# blinds_v60.net
KiCad netlist of a schematic drawn in EAGLE
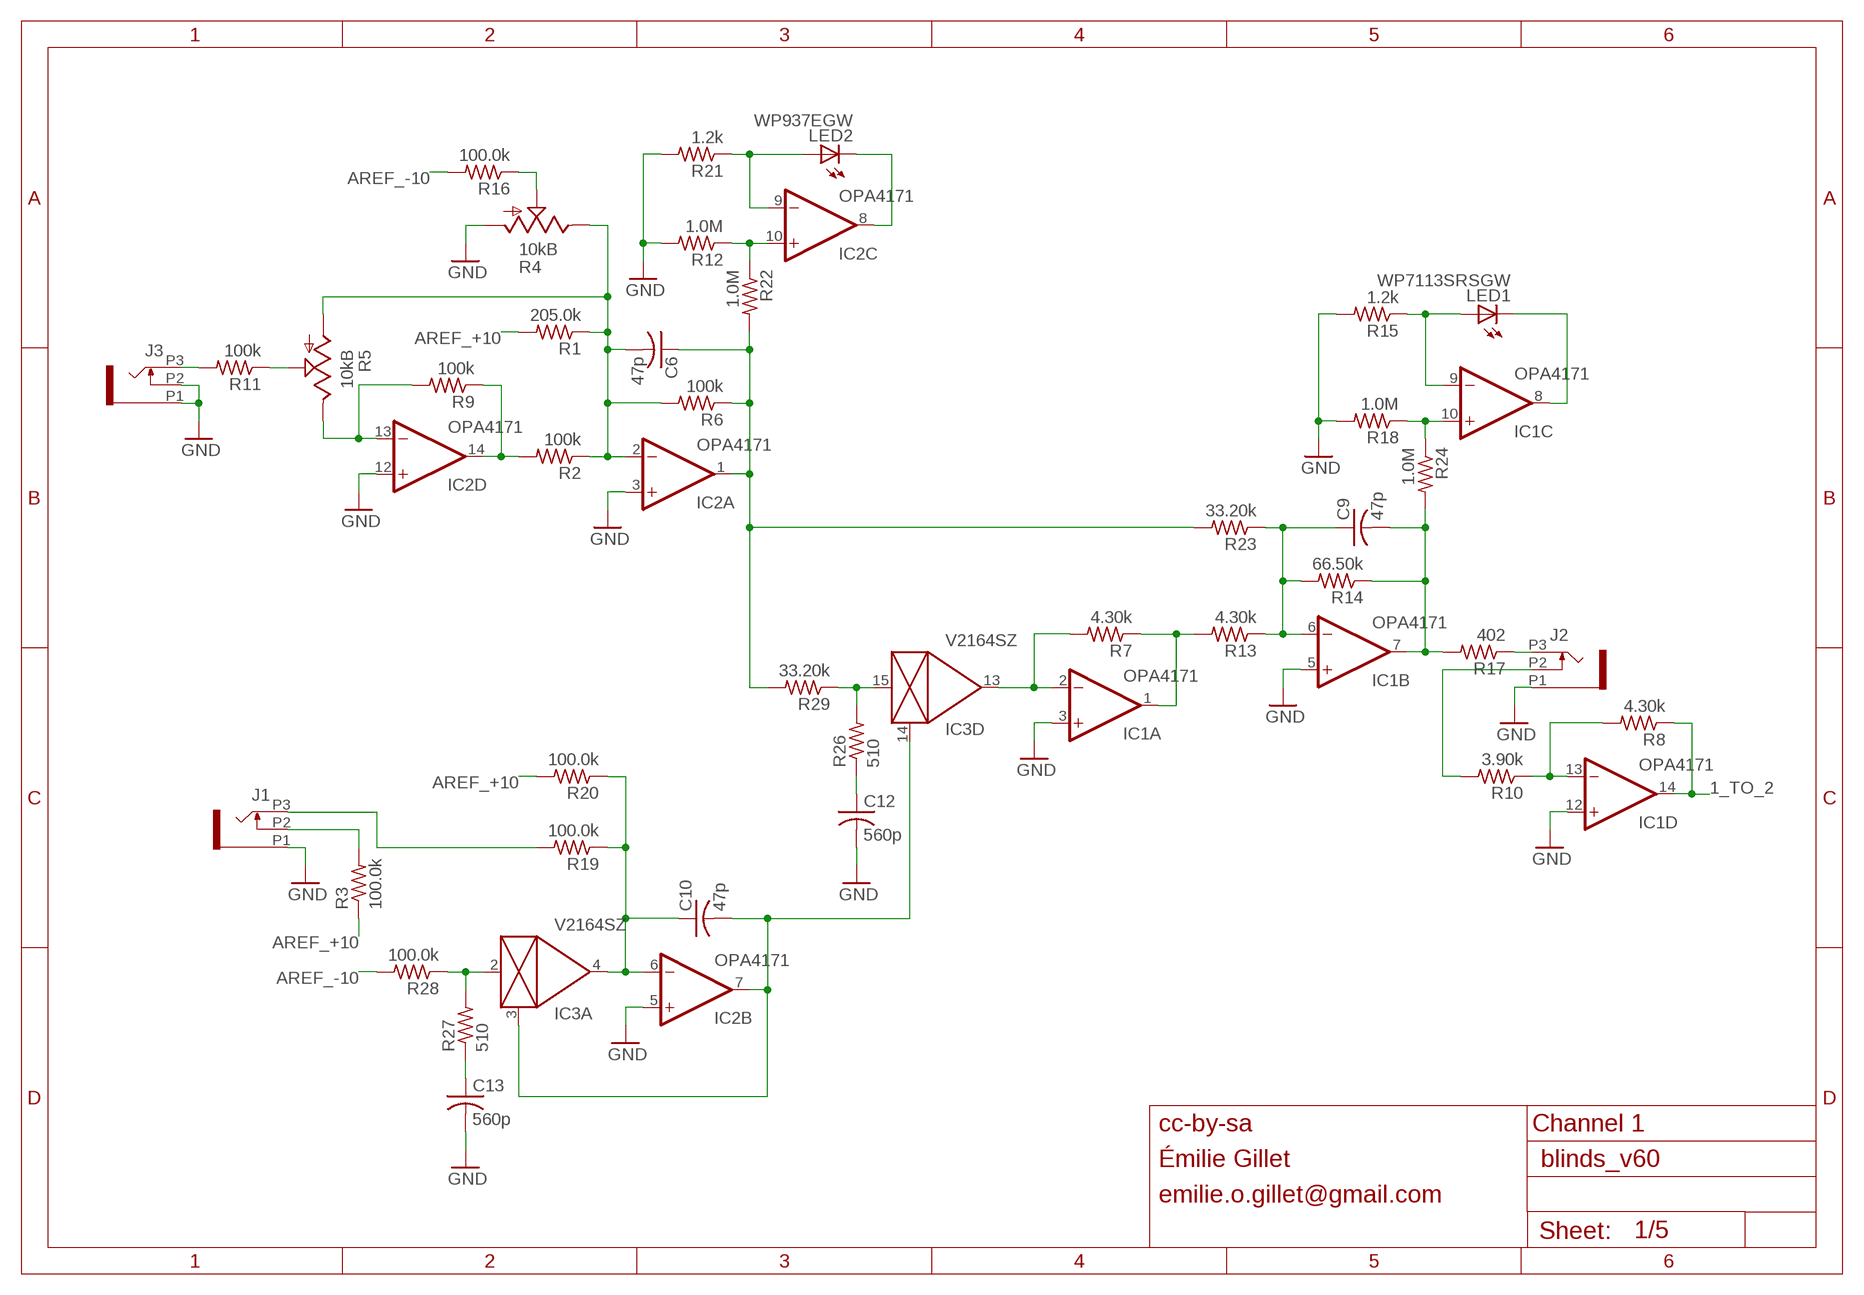
[diagram p0: schematic, sheet 1]
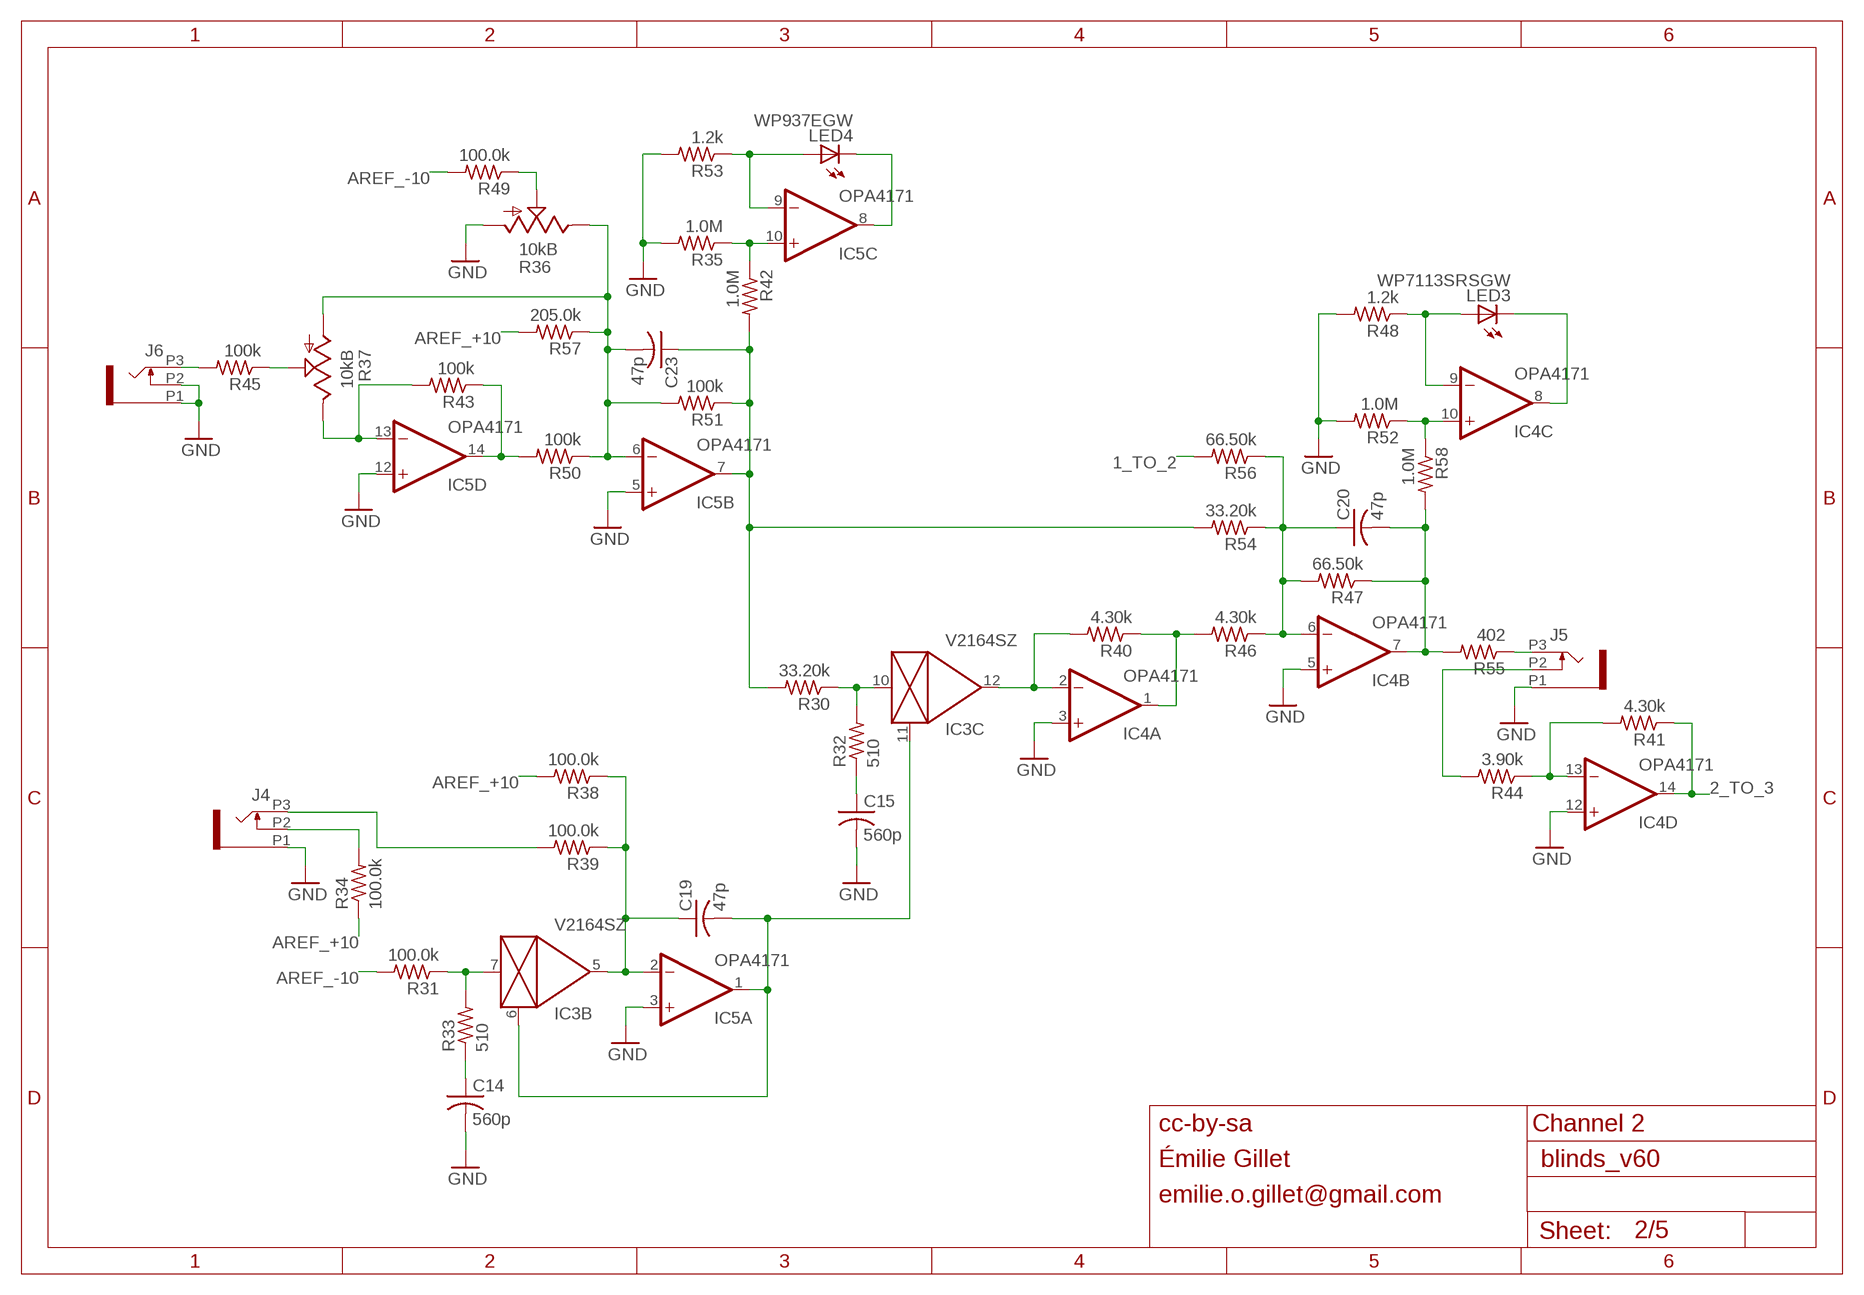
[diagram p1: schematic, sheet 2]
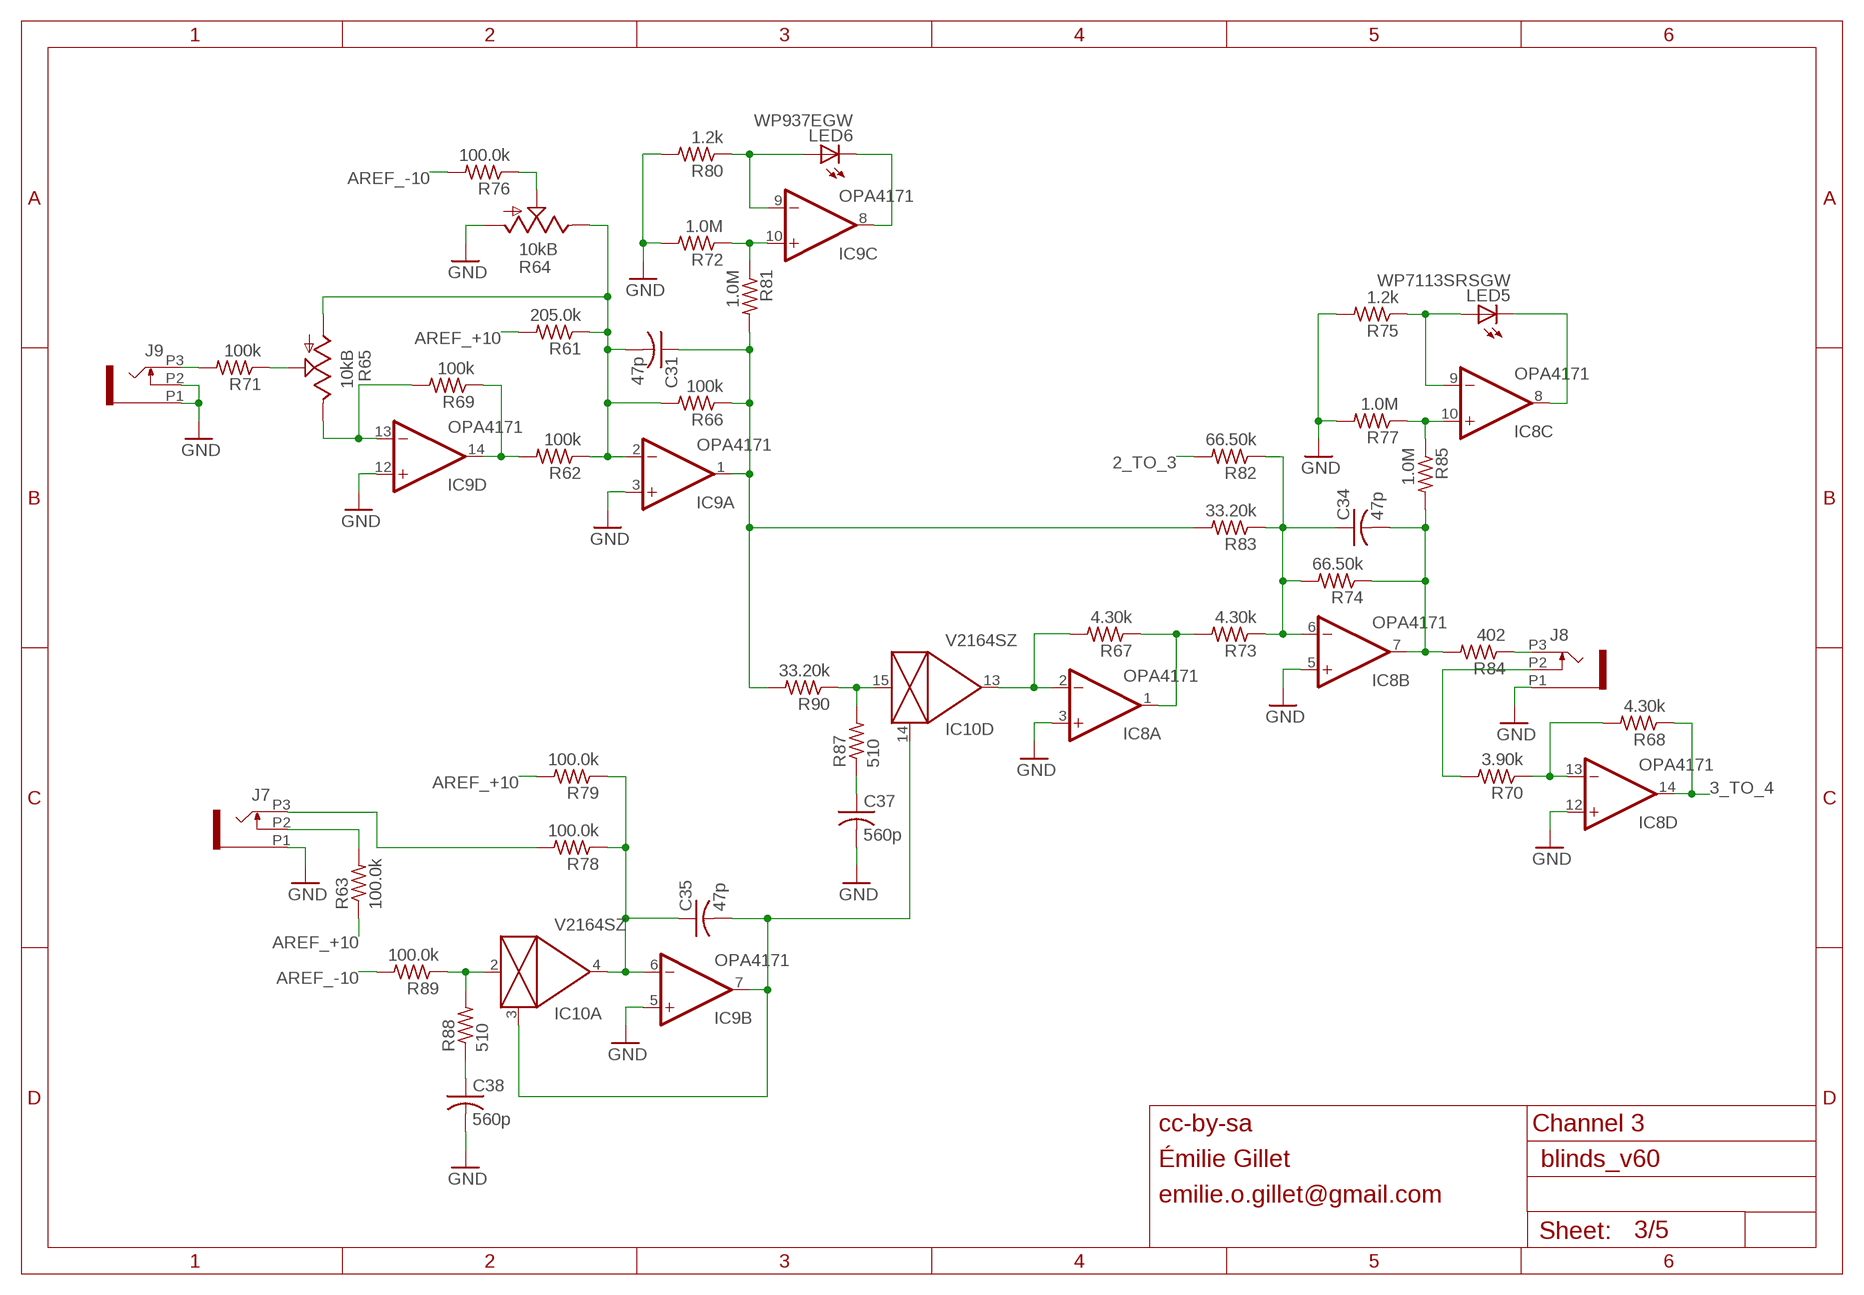
[diagram p2: schematic, sheet 3]
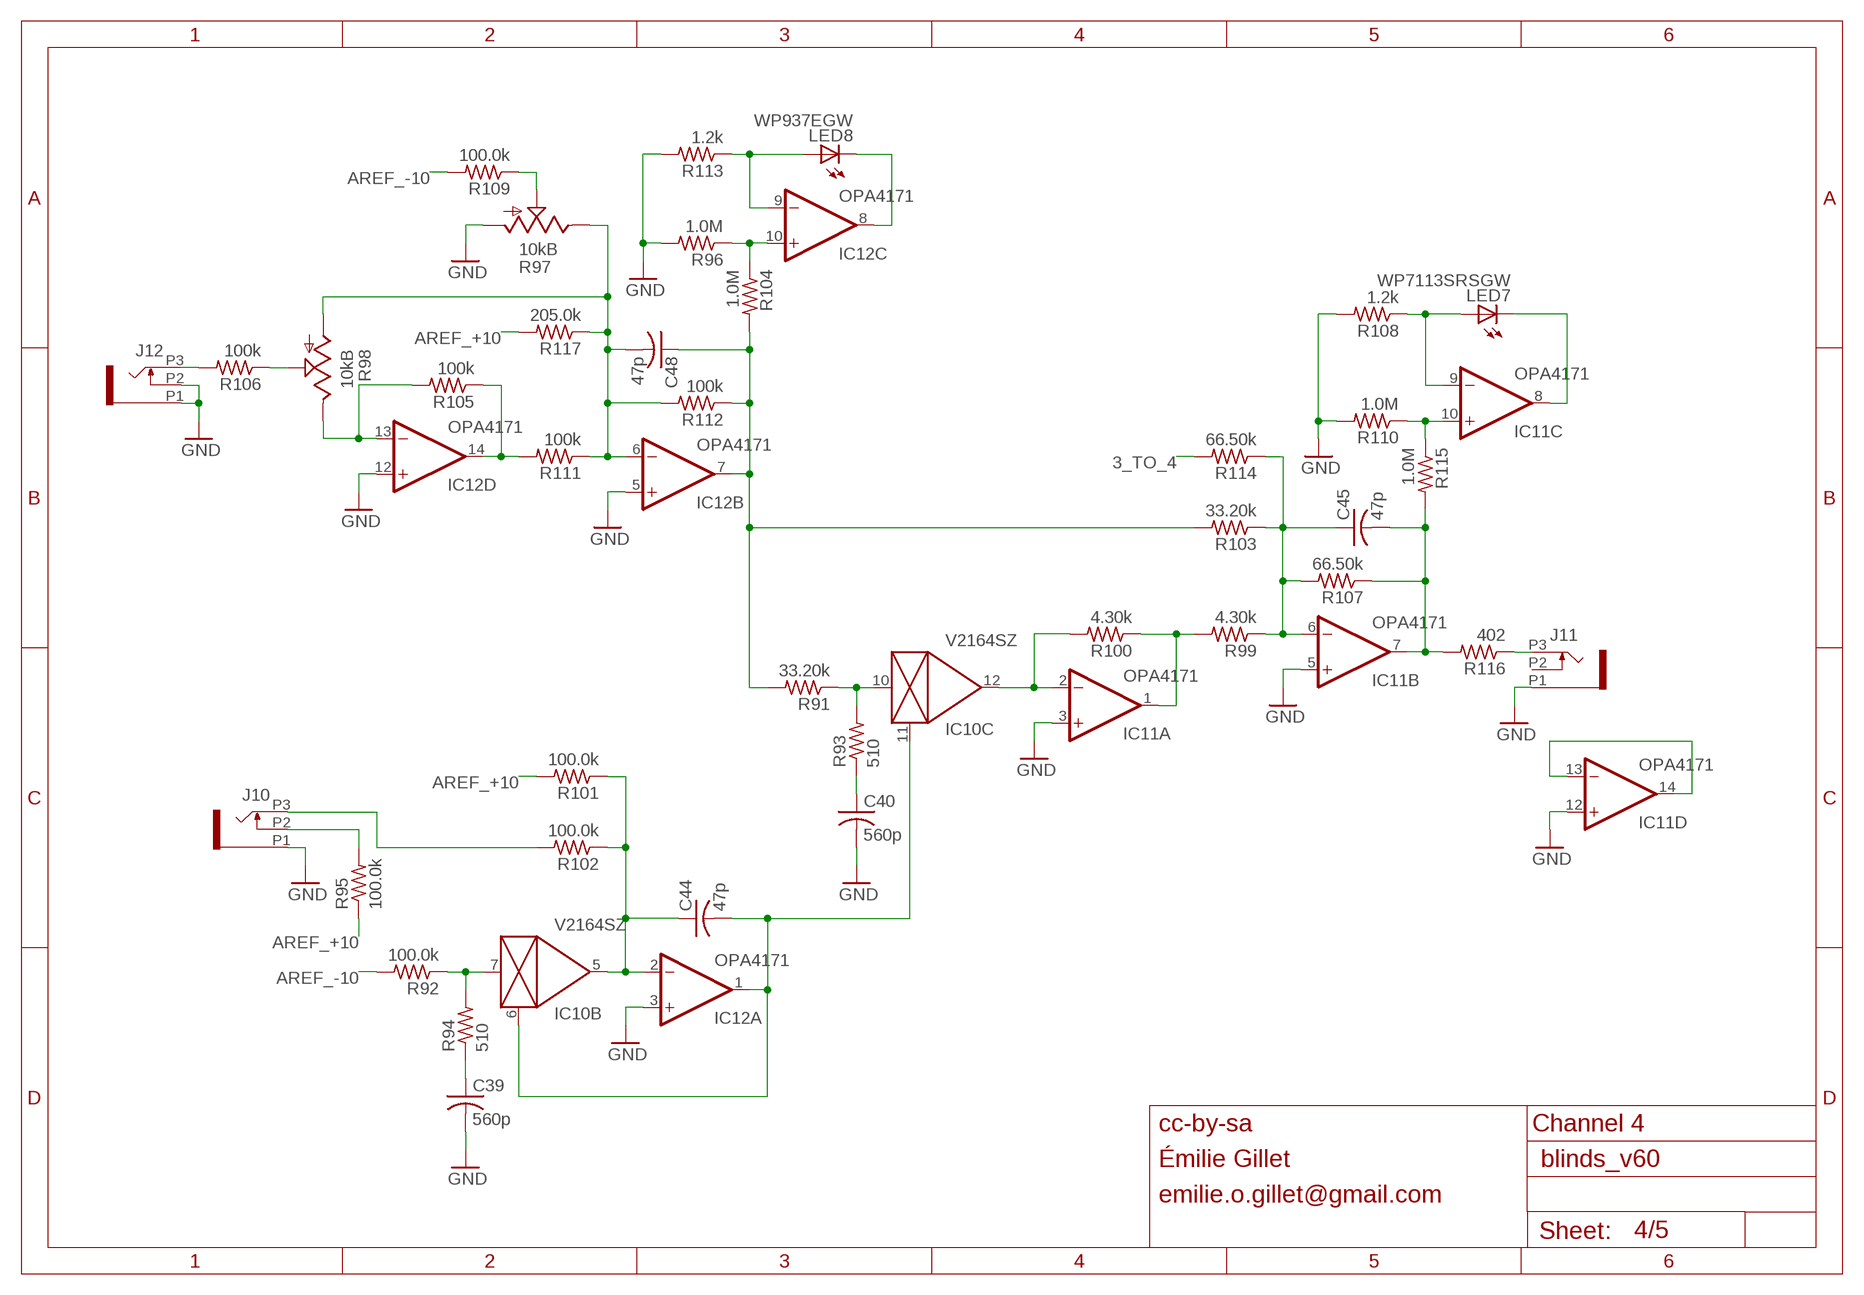
[diagram p3: schematic, sheet 4]
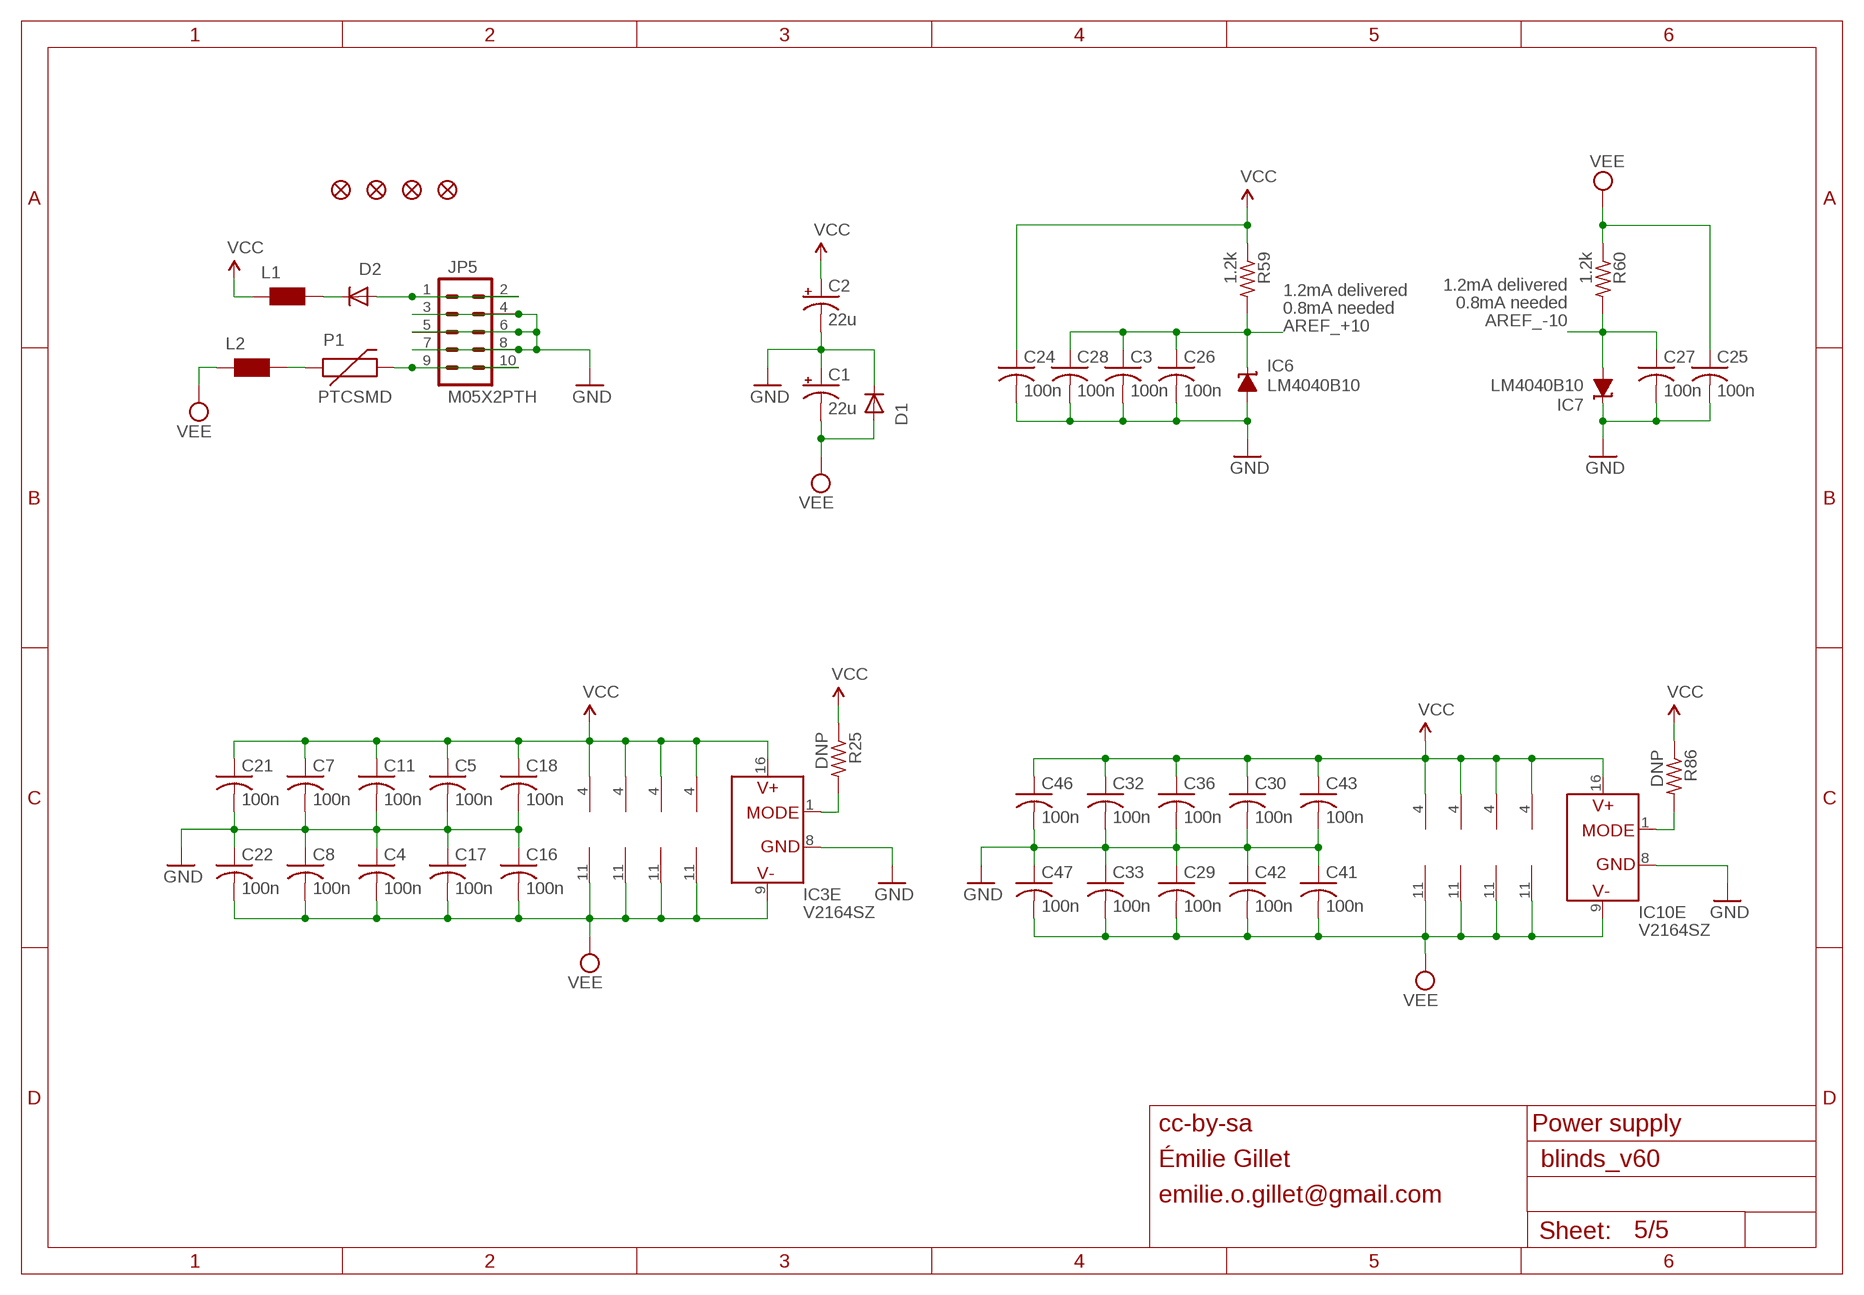
[diagram p4: schematic, sheet 5]

(export (version "E")
  (design (tool "Eeschema 10.0.6"))
  (components
    (comp (ref "C1")
      (value "22u")
      (footprint "eagle-import:PANASONIC_C")
      (libsource (lib "eagle-import") (part "CPOL-USC"))
    )
    (comp (ref "C2")
      (value "22u")
      (footprint "eagle-import:PANASONIC_C")
      (libsource (lib "eagle-import") (part "CPOL-USC"))
    )
    (comp (ref "C3")
      (value "100n")
      (footprint "eagle-import:C0603")
      (libsource (lib "eagle-import") (part "C-USC0603"))
    )
    (comp (ref "C4")
      (value "100n")
      (footprint "eagle-import:C0603")
      (libsource (lib "eagle-import") (part "C-USC0603"))
    )
    (comp (ref "C5")
      (value "100n")
      (footprint "eagle-import:C0603")
      (libsource (lib "eagle-import") (part "C-USC0603"))
    )
    (comp (ref "C7")
      (value "100n")
      (footprint "eagle-import:C0603")
      (libsource (lib "eagle-import") (part "C-USC0603"))
    )
    (comp (ref "C8")
      (value "100n")
      (footprint "eagle-import:C0603")
      (libsource (lib "eagle-import") (part "C-USC0603"))
    )
    (comp (ref "C11")
      (value "100n")
      (footprint "eagle-import:C0603")
      (libsource (lib "eagle-import") (part "C-USC0603"))
    )
    (comp (ref "C16")
      (value "100n")
      (footprint "eagle-import:C0603")
      (libsource (lib "eagle-import") (part "C-USC0603"))
    )
    (comp (ref "C17")
      (value "100n")
      (footprint "eagle-import:C0603")
      (libsource (lib "eagle-import") (part "C-USC0603"))
    )
    (comp (ref "C18")
      (value "100n")
      (footprint "eagle-import:C0603")
      (libsource (lib "eagle-import") (part "C-USC0603"))
    )
    (comp (ref "C21")
      (value "100n")
      (footprint "eagle-import:C0603")
      (libsource (lib "eagle-import") (part "C-USC0603"))
    )
    (comp (ref "C22")
      (value "100n")
      (footprint "eagle-import:C0603")
      (libsource (lib "eagle-import") (part "C-USC0603"))
    )
    (comp (ref "C24")
      (value "100n")
      (footprint "eagle-import:C0603")
      (libsource (lib "eagle-import") (part "C-USC0603"))
    )
    (comp (ref "C25")
      (value "100n")
      (footprint "eagle-import:C0603")
      (libsource (lib "eagle-import") (part "C-USC0603"))
    )
    (comp (ref "C26")
      (value "100n")
      (footprint "eagle-import:C0603")
      (libsource (lib "eagle-import") (part "C-USC0603"))
    )
    (comp (ref "C27")
      (value "100n")
      (footprint "eagle-import:C0603")
      (libsource (lib "eagle-import") (part "C-USC0603"))
    )
    (comp (ref "C28")
      (value "100n")
      (footprint "eagle-import:C0603")
      (libsource (lib "eagle-import") (part "C-USC0603"))
    )
    (comp (ref "C29")
      (value "100n")
      (footprint "eagle-import:C0603")
      (libsource (lib "eagle-import") (part "C-USC0603"))
    )
    (comp (ref "C30")
      (value "100n")
      (footprint "eagle-import:C0603")
      (libsource (lib "eagle-import") (part "C-USC0603"))
    )
    (comp (ref "C32")
      (value "100n")
      (footprint "eagle-import:C0603")
      (libsource (lib "eagle-import") (part "C-USC0603"))
    )
    (comp (ref "C33")
      (value "100n")
      (footprint "eagle-import:C0603")
      (libsource (lib "eagle-import") (part "C-USC0603"))
    )
    (comp (ref "C36")
      (value "100n")
      (footprint "eagle-import:C0603")
      (libsource (lib "eagle-import") (part "C-USC0603"))
    )
    (comp (ref "C41")
      (value "100n")
      (footprint "eagle-import:C0603")
      (libsource (lib "eagle-import") (part "C-USC0603"))
    )
    (comp (ref "C42")
      (value "100n")
      (footprint "eagle-import:C0603")
      (libsource (lib "eagle-import") (part "C-USC0603"))
    )
    (comp (ref "C43")
      (value "100n")
      (footprint "eagle-import:C0603")
      (libsource (lib "eagle-import") (part "C-USC0603"))
    )
    (comp (ref "C46")
      (value "100n")
      (footprint "eagle-import:C0603")
      (libsource (lib "eagle-import") (part "C-USC0603"))
    )
    (comp (ref "C47")
      (value "100n")
      (footprint "eagle-import:C0603")
      (libsource (lib "eagle-import") (part "C-USC0603"))
    )
    (comp (ref "D1")
      (value "1N5819HW")
      (footprint "eagle-import:SOD123")
      (libsource (lib "eagle-import") (part "DIODE-SOD123"))
    )
    (comp (ref "D2")
      (value "1N5819HW")
      (footprint "eagle-import:SOD123")
      (libsource (lib "eagle-import") (part "DIODE-SOD123"))
    )
    (comp (ref "IC1")
      (value "OPA4171")
      (footprint "eagle-import:TSSOP14")
      (libsource (lib "eagle-import") (part "TL074PW"))
    )
    (comp (ref "IC2")
      (value "OPA4171")
      (footprint "eagle-import:TSSOP14")
      (libsource (lib "eagle-import") (part "TL074PW"))
    )
    (comp (ref "IC3")
      (value "V2164SZ")
      (footprint "eagle-import:SOIC16N")
      (libsource (lib "eagle-import") (part "SSM2164S"))
    )
    (comp (ref "IC4")
      (value "OPA4171")
      (footprint "eagle-import:TSSOP14")
      (libsource (lib "eagle-import") (part "TL074PW"))
    )
    (comp (ref "IC5")
      (value "OPA4171")
      (footprint "eagle-import:TSSOP14")
      (libsource (lib "eagle-import") (part "TL074PW"))
    )
    (comp (ref "IC6")
      (value "LM4040B10")
      (footprint "eagle-import:DBZ_R-PDSO-G3")
      (libsource (lib "eagle-import") (part "LM4041DBZB12"))
    )
    (comp (ref "IC7")
      (value "LM4040B10")
      (footprint "eagle-import:DBZ_R-PDSO-G3")
      (libsource (lib "eagle-import") (part "LM4041DBZB12"))
    )
    (comp (ref "IC8")
      (value "OPA4171")
      (footprint "eagle-import:TSSOP14")
      (libsource (lib "eagle-import") (part "TL074PW"))
    )
    (comp (ref "IC9")
      (value "OPA4171")
      (footprint "eagle-import:TSSOP14")
      (libsource (lib "eagle-import") (part "TL074PW"))
    )
    (comp (ref "IC10")
      (value "V2164SZ")
      (footprint "eagle-import:SOIC16N")
      (libsource (lib "eagle-import") (part "SSM2164S"))
    )
    (comp (ref "IC11")
      (value "OPA4171")
      (footprint "eagle-import:TSSOP14")
      (libsource (lib "eagle-import") (part "TL074PW"))
    )
    (comp (ref "IC12")
      (value "OPA4171")
      (footprint "eagle-import:TSSOP14")
      (libsource (lib "eagle-import") (part "TL074PW"))
    )
    (comp (ref "JP1")
      (value "FIDUCIAL1X2")
      (footprint "eagle-import:FIDUCIAL-1X2")
      (libsource (lib "eagle-import") (part "FIDUCIAL1X2"))
    )
    (comp (ref "JP2")
      (value "FIDUCIAL1X2")
      (footprint "eagle-import:FIDUCIAL-1X2")
      (libsource (lib "eagle-import") (part "FIDUCIAL1X2"))
    )
    (comp (ref "JP3")
      (value "FIDUCIAL1X2")
      (footprint "eagle-import:FIDUCIAL-1X2")
      (libsource (lib "eagle-import") (part "FIDUCIAL1X2"))
    )
    (comp (ref "JP4")
      (value "FIDUCIAL1X2")
      (footprint "eagle-import:FIDUCIAL-1X2")
      (libsource (lib "eagle-import") (part "FIDUCIAL1X2"))
    )
    (comp (ref "JP5")
      (value "M05X2PTH")
      (footprint "eagle-import:AVR_ICSP")
      (libsource (lib "eagle-import") (part "M05X2PTH"))
    )
    (comp (ref "L1")
      (value "WE-CBF_0603")
      (footprint "eagle-import:0603")
      (libsource (lib "eagle-import") (part "WE-CBF_0603"))
    )
    (comp (ref "L2")
      (value "WE-CBF_0603")
      (footprint "eagle-import:0603")
      (libsource (lib "eagle-import") (part "WE-CBF_0603"))
    )
    (comp (ref "P1")
      (value "PTCSMD")
      (footprint "eagle-import:PTC-1206")
      (libsource (lib "eagle-import") (part "PTCSMD"))
    )
    (comp (ref "R25")
      (value "DNP")
      (footprint "eagle-import:R0603")
      (libsource (lib "eagle-import") (part "R-US_R0603"))
    )
    (comp (ref "R59")
      (value "1.2k")
      (footprint "eagle-import:R0603")
      (libsource (lib "eagle-import") (part "R-US_R0603"))
    )
    (comp (ref "R60")
      (value "1.2k")
      (footprint "eagle-import:R0603")
      (libsource (lib "eagle-import") (part "R-US_R0603"))
    )
    (comp (ref "R86")
      (value "DNP")
      (footprint "eagle-import:R0603")
      (libsource (lib "eagle-import") (part "R-US_R0603"))
    )
    (comp (ref "C31")
      (value "47p")
      (footprint "eagle-import:C0603")
      (libsource (lib "eagle-import") (part "C-USC0603"))
    )
    (comp (ref "C34")
      (value "47p")
      (footprint "eagle-import:C0603")
      (libsource (lib "eagle-import") (part "C-USC0603"))
    )
    (comp (ref "C35")
      (value "47p")
      (footprint "eagle-import:C0603")
      (libsource (lib "eagle-import") (part "C-USC0603"))
    )
    (comp (ref "C37")
      (value "560p")
      (footprint "eagle-import:C0603")
      (libsource (lib "eagle-import") (part "C-USC0603"))
    )
    (comp (ref "C38")
      (value "560p")
      (footprint "eagle-import:C0603")
      (libsource (lib "eagle-import") (part "C-USC0603"))
    )
    (comp (ref "J7")
      (value "PJ301_THONKICONN6")
      (footprint "eagle-import:WQP_PJ_301M6")
      (libsource (lib "eagle-import") (part "PJ301_THONKICONN6"))
    )
    (comp (ref "J8")
      (value "PJ301_THONKICONN6")
      (footprint "eagle-import:WQP_PJ_301M6")
      (libsource (lib "eagle-import") (part "PJ301_THONKICONN6"))
    )
    (comp (ref "J9")
      (value "PJ301_THONKICONN6")
      (footprint "eagle-import:WQP_PJ_301M6")
      (libsource (lib "eagle-import") (part "PJ301_THONKICONN6"))
    )
    (comp (ref "LED5")
      (value "WP7113SRSGW")
      (footprint "eagle-import:LED5MM")
      (libsource (lib "eagle-import") (part "LED5MM"))
    )
    (comp (ref "LED6")
      (value "WP937EGW")
      (footprint "eagle-import:LED3MM")
      (libsource (lib "eagle-import") (part "LED3MM"))
    )
    (comp (ref "R61")
      (value "205.0k")
      (footprint "eagle-import:R0603")
      (libsource (lib "eagle-import") (part "R-US_R0603"))
    )
    (comp (ref "R62")
      (value "100k")
      (footprint "eagle-import:R0603")
      (libsource (lib "eagle-import") (part "R-US_R0603"))
    )
    (comp (ref "R63")
      (value "100.0k")
      (footprint "eagle-import:R0603")
      (libsource (lib "eagle-import") (part "R-US_R0603"))
    )
    (comp (ref "R64")
      (value "10kB")
      (footprint "eagle-import:ALPS_POT_VERTICAL_PS")
      (libsource (lib "eagle-import") (part "POT_USVERTICAL_PS"))
    )
    (comp (ref "R65")
      (value "10kB")
      (footprint "eagle-import:ALPS_POT_VERTICAL")
      (libsource (lib "eagle-import") (part "POT_USVERTICAL"))
    )
    (comp (ref "R66")
      (value "100k")
      (footprint "eagle-import:R0603")
      (libsource (lib "eagle-import") (part "R-US_R0603"))
    )
    (comp (ref "R67")
      (value "4.30k")
      (footprint "eagle-import:R0603")
      (libsource (lib "eagle-import") (part "R-US_R0603"))
    )
    (comp (ref "R68")
      (value "4.30k")
      (footprint "eagle-import:R0603")
      (libsource (lib "eagle-import") (part "R-US_R0603"))
    )
    (comp (ref "R69")
      (value "100k")
      (footprint "eagle-import:R0603")
      (libsource (lib "eagle-import") (part "R-US_R0603"))
    )
    (comp (ref "R70")
      (value "3.90k")
      (footprint "eagle-import:R0603")
      (libsource (lib "eagle-import") (part "R-US_R0603"))
    )
    (comp (ref "R71")
      (value "100k")
      (footprint "eagle-import:R0603")
      (libsource (lib "eagle-import") (part "R-US_R0603"))
    )
    (comp (ref "R72")
      (value "1.0M")
      (footprint "eagle-import:R0603")
      (libsource (lib "eagle-import") (part "R-US_R0603"))
    )
    (comp (ref "R73")
      (value "4.30k")
      (footprint "eagle-import:R0603")
      (libsource (lib "eagle-import") (part "R-US_R0603"))
    )
    (comp (ref "R74")
      (value "66.50k")
      (footprint "eagle-import:R0603")
      (libsource (lib "eagle-import") (part "R-US_R0603"))
    )
    (comp (ref "R75")
      (value "1.2k")
      (footprint "eagle-import:R0603")
      (libsource (lib "eagle-import") (part "R-US_R0603"))
    )
    (comp (ref "R76")
      (value "100.0k")
      (footprint "eagle-import:R0603")
      (libsource (lib "eagle-import") (part "R-US_R0603"))
    )
    (comp (ref "R77")
      (value "1.0M")
      (footprint "eagle-import:R0603")
      (libsource (lib "eagle-import") (part "R-US_R0603"))
    )
    (comp (ref "R78")
      (value "100.0k")
      (footprint "eagle-import:R0603")
      (libsource (lib "eagle-import") (part "R-US_R0603"))
    )
    (comp (ref "R79")
      (value "100.0k")
      (footprint "eagle-import:R0603")
      (libsource (lib "eagle-import") (part "R-US_R0603"))
    )
    (comp (ref "R80")
      (value "1.2k")
      (footprint "eagle-import:R0603")
      (libsource (lib "eagle-import") (part "R-US_R0603"))
    )
    (comp (ref "R81")
      (value "1.0M")
      (footprint "eagle-import:R0603")
      (libsource (lib "eagle-import") (part "R-US_R0603"))
    )
    (comp (ref "R82")
      (value "66.50k")
      (footprint "eagle-import:R0603")
      (libsource (lib "eagle-import") (part "R-US_R0603"))
    )
    (comp (ref "R83")
      (value "33.20k")
      (footprint "eagle-import:R0603")
      (libsource (lib "eagle-import") (part "R-US_R0603"))
    )
    (comp (ref "R84")
      (value "402")
      (footprint "eagle-import:R0603")
      (libsource (lib "eagle-import") (part "R-US_R0603"))
    )
    (comp (ref "R85")
      (value "1.0M")
      (footprint "eagle-import:R0603")
      (libsource (lib "eagle-import") (part "R-US_R0603"))
    )
    (comp (ref "R87")
      (value "510")
      (footprint "eagle-import:R0603")
      (libsource (lib "eagle-import") (part "R-US_R0603"))
    )
    (comp (ref "R88")
      (value "510")
      (footprint "eagle-import:R0603")
      (libsource (lib "eagle-import") (part "R-US_R0603"))
    )
    (comp (ref "R89")
      (value "100.0k")
      (footprint "eagle-import:R0603")
      (libsource (lib "eagle-import") (part "R-US_R0603"))
    )
    (comp (ref "R90")
      (value "33.20k")
      (footprint "eagle-import:R0603")
      (libsource (lib "eagle-import") (part "R-US_R0603"))
    )
    (comp (ref "C14")
      (value "560p")
      (footprint "eagle-import:C0603")
      (libsource (lib "eagle-import") (part "C-USC0603"))
    )
    (comp (ref "C15")
      (value "560p")
      (footprint "eagle-import:C0603")
      (libsource (lib "eagle-import") (part "C-USC0603"))
    )
    (comp (ref "C19")
      (value "47p")
      (footprint "eagle-import:C0603")
      (libsource (lib "eagle-import") (part "C-USC0603"))
    )
    (comp (ref "C20")
      (value "47p")
      (footprint "eagle-import:C0603")
      (libsource (lib "eagle-import") (part "C-USC0603"))
    )
    (comp (ref "C23")
      (value "47p")
      (footprint "eagle-import:C0603")
      (libsource (lib "eagle-import") (part "C-USC0603"))
    )
    (comp (ref "J4")
      (value "PJ301_THONKICONN6")
      (footprint "eagle-import:WQP_PJ_301M6")
      (libsource (lib "eagle-import") (part "PJ301_THONKICONN6"))
    )
    (comp (ref "J5")
      (value "PJ301_THONKICONN6")
      (footprint "eagle-import:WQP_PJ_301M6")
      (libsource (lib "eagle-import") (part "PJ301_THONKICONN6"))
    )
    (comp (ref "J6")
      (value "PJ301_THONKICONN6")
      (footprint "eagle-import:WQP_PJ_301M6")
      (libsource (lib "eagle-import") (part "PJ301_THONKICONN6"))
    )
    (comp (ref "LED3")
      (value "WP7113SRSGW")
      (footprint "eagle-import:LED5MM")
      (libsource (lib "eagle-import") (part "LED5MM"))
    )
    (comp (ref "LED4")
      (value "WP937EGW")
      (footprint "eagle-import:LED3MM")
      (libsource (lib "eagle-import") (part "LED3MM"))
    )
    (comp (ref "R30")
      (value "33.20k")
      (footprint "eagle-import:R0603")
      (libsource (lib "eagle-import") (part "R-US_R0603"))
    )
    (comp (ref "R31")
      (value "100.0k")
      (footprint "eagle-import:R0603")
      (libsource (lib "eagle-import") (part "R-US_R0603"))
    )
    (comp (ref "R32")
      (value "510")
      (footprint "eagle-import:R0603")
      (libsource (lib "eagle-import") (part "R-US_R0603"))
    )
    (comp (ref "R33")
      (value "510")
      (footprint "eagle-import:R0603")
      (libsource (lib "eagle-import") (part "R-US_R0603"))
    )
    (comp (ref "R34")
      (value "100.0k")
      (footprint "eagle-import:R0603")
      (libsource (lib "eagle-import") (part "R-US_R0603"))
    )
    (comp (ref "R35")
      (value "1.0M")
      (footprint "eagle-import:R0603")
      (libsource (lib "eagle-import") (part "R-US_R0603"))
    )
    (comp (ref "R36")
      (value "10kB")
      (footprint "eagle-import:ALPS_POT_VERTICAL_PS")
      (libsource (lib "eagle-import") (part "POT_USVERTICAL_PS"))
    )
    (comp (ref "R37")
      (value "10kB")
      (footprint "eagle-import:ALPS_POT_VERTICAL")
      (libsource (lib "eagle-import") (part "POT_USVERTICAL"))
    )
    (comp (ref "R38")
      (value "100.0k")
      (footprint "eagle-import:R0603")
      (libsource (lib "eagle-import") (part "R-US_R0603"))
    )
    (comp (ref "R39")
      (value "100.0k")
      (footprint "eagle-import:R0603")
      (libsource (lib "eagle-import") (part "R-US_R0603"))
    )
    (comp (ref "R40")
      (value "4.30k")
      (footprint "eagle-import:R0603")
      (libsource (lib "eagle-import") (part "R-US_R0603"))
    )
    (comp (ref "R41")
      (value "4.30k")
      (footprint "eagle-import:R0603")
      (libsource (lib "eagle-import") (part "R-US_R0603"))
    )
    (comp (ref "R42")
      (value "1.0M")
      (footprint "eagle-import:R0603")
      (libsource (lib "eagle-import") (part "R-US_R0603"))
    )
    (comp (ref "R43")
      (value "100k")
      (footprint "eagle-import:R0603")
      (libsource (lib "eagle-import") (part "R-US_R0603"))
    )
    (comp (ref "R44")
      (value "3.90k")
      (footprint "eagle-import:R0603")
      (libsource (lib "eagle-import") (part "R-US_R0603"))
    )
    (comp (ref "R45")
      (value "100k")
      (footprint "eagle-import:R0603")
      (libsource (lib "eagle-import") (part "R-US_R0603"))
    )
    (comp (ref "R46")
      (value "4.30k")
      (footprint "eagle-import:R0603")
      (libsource (lib "eagle-import") (part "R-US_R0603"))
    )
    (comp (ref "R47")
      (value "66.50k")
      (footprint "eagle-import:R0603")
      (libsource (lib "eagle-import") (part "R-US_R0603"))
    )
    (comp (ref "R48")
      (value "1.2k")
      (footprint "eagle-import:R0603")
      (libsource (lib "eagle-import") (part "R-US_R0603"))
    )
    (comp (ref "R49")
      (value "100.0k")
      (footprint "eagle-import:R0603")
      (libsource (lib "eagle-import") (part "R-US_R0603"))
    )
    (comp (ref "R50")
      (value "100k")
      (footprint "eagle-import:R0603")
      (libsource (lib "eagle-import") (part "R-US_R0603"))
    )
    (comp (ref "R51")
      (value "100k")
      (footprint "eagle-import:R0603")
      (libsource (lib "eagle-import") (part "R-US_R0603"))
    )
    (comp (ref "R52")
      (value "1.0M")
      (footprint "eagle-import:R0603")
      (libsource (lib "eagle-import") (part "R-US_R0603"))
    )
    (comp (ref "R53")
      (value "1.2k")
      (footprint "eagle-import:R0603")
      (libsource (lib "eagle-import") (part "R-US_R0603"))
    )
    (comp (ref "R54")
      (value "33.20k")
      (footprint "eagle-import:R0603")
      (libsource (lib "eagle-import") (part "R-US_R0603"))
    )
    (comp (ref "R55")
      (value "402")
      (footprint "eagle-import:R0603")
      (libsource (lib "eagle-import") (part "R-US_R0603"))
    )
    (comp (ref "R56")
      (value "66.50k")
      (footprint "eagle-import:R0603")
      (libsource (lib "eagle-import") (part "R-US_R0603"))
    )
    (comp (ref "R57")
      (value "205.0k")
      (footprint "eagle-import:R0603")
      (libsource (lib "eagle-import") (part "R-US_R0603"))
    )
    (comp (ref "R58")
      (value "1.0M")
      (footprint "eagle-import:R0603")
      (libsource (lib "eagle-import") (part "R-US_R0603"))
    )
    (comp (ref "C6")
      (value "47p")
      (footprint "eagle-import:C0603")
      (libsource (lib "eagle-import") (part "C-USC0603"))
    )
    (comp (ref "C9")
      (value "47p")
      (footprint "eagle-import:C0603")
      (libsource (lib "eagle-import") (part "C-USC0603"))
    )
    (comp (ref "C10")
      (value "47p")
      (footprint "eagle-import:C0603")
      (libsource (lib "eagle-import") (part "C-USC0603"))
    )
    (comp (ref "C12")
      (value "560p")
      (footprint "eagle-import:C0603")
      (libsource (lib "eagle-import") (part "C-USC0603"))
    )
    (comp (ref "C13")
      (value "560p")
      (footprint "eagle-import:C0603")
      (libsource (lib "eagle-import") (part "C-USC0603"))
    )
    (comp (ref "J1")
      (value "PJ301_THONKICONN6")
      (footprint "eagle-import:WQP_PJ_301M6")
      (libsource (lib "eagle-import") (part "PJ301_THONKICONN6"))
    )
    (comp (ref "J2")
      (value "PJ301_THONKICONN6")
      (footprint "eagle-import:WQP_PJ_301M6")
      (libsource (lib "eagle-import") (part "PJ301_THONKICONN6"))
    )
    (comp (ref "J3")
      (value "PJ301_THONKICONN6")
      (footprint "eagle-import:WQP_PJ_301M6")
      (libsource (lib "eagle-import") (part "PJ301_THONKICONN6"))
    )
    (comp (ref "LED1")
      (value "WP7113SRSGW")
      (footprint "eagle-import:LED5MM")
      (libsource (lib "eagle-import") (part "LED5MM"))
    )
    (comp (ref "LED2")
      (value "WP937EGW")
      (footprint "eagle-import:LED3MM")
      (libsource (lib "eagle-import") (part "LED3MM"))
    )
    (comp (ref "R1")
      (value "205.0k")
      (footprint "eagle-import:R0603")
      (libsource (lib "eagle-import") (part "R-US_R0603"))
    )
    (comp (ref "R2")
      (value "100k")
      (footprint "eagle-import:R0603")
      (libsource (lib "eagle-import") (part "R-US_R0603"))
    )
    (comp (ref "R3")
      (value "100.0k")
      (footprint "eagle-import:R0603")
      (libsource (lib "eagle-import") (part "R-US_R0603"))
    )
    (comp (ref "R4")
      (value "10kB")
      (footprint "eagle-import:ALPS_POT_VERTICAL_PS")
      (libsource (lib "eagle-import") (part "POT_USVERTICAL_PS"))
    )
    (comp (ref "R5")
      (value "10kB")
      (footprint "eagle-import:ALPS_POT_VERTICAL")
      (libsource (lib "eagle-import") (part "POT_USVERTICAL"))
    )
    (comp (ref "R6")
      (value "100k")
      (footprint "eagle-import:R0603")
      (libsource (lib "eagle-import") (part "R-US_R0603"))
    )
    (comp (ref "R7")
      (value "4.30k")
      (footprint "eagle-import:R0603")
      (libsource (lib "eagle-import") (part "R-US_R0603"))
    )
    (comp (ref "R8")
      (value "4.30k")
      (footprint "eagle-import:R0603")
      (libsource (lib "eagle-import") (part "R-US_R0603"))
    )
    (comp (ref "R9")
      (value "100k")
      (footprint "eagle-import:R0603")
      (libsource (lib "eagle-import") (part "R-US_R0603"))
    )
    (comp (ref "R10")
      (value "3.90k")
      (footprint "eagle-import:R0603")
      (libsource (lib "eagle-import") (part "R-US_R0603"))
    )
    (comp (ref "R11")
      (value "100k")
      (footprint "eagle-import:R0603")
      (libsource (lib "eagle-import") (part "R-US_R0603"))
    )
    (comp (ref "R12")
      (value "1.0M")
      (footprint "eagle-import:R0603")
      (libsource (lib "eagle-import") (part "R-US_R0603"))
    )
    (comp (ref "R13")
      (value "4.30k")
      (footprint "eagle-import:R0603")
      (libsource (lib "eagle-import") (part "R-US_R0603"))
    )
    (comp (ref "R14")
      (value "66.50k")
      (footprint "eagle-import:R0603")
      (libsource (lib "eagle-import") (part "R-US_R0603"))
    )
    (comp (ref "R15")
      (value "1.2k")
      (footprint "eagle-import:R0603")
      (libsource (lib "eagle-import") (part "R-US_R0603"))
    )
    (comp (ref "R16")
      (value "100.0k")
      (footprint "eagle-import:R0603")
      (libsource (lib "eagle-import") (part "R-US_R0603"))
    )
    (comp (ref "R17")
      (value "402")
      (footprint "eagle-import:R0603")
      (libsource (lib "eagle-import") (part "R-US_R0603"))
    )
    (comp (ref "R18")
      (value "1.0M")
      (footprint "eagle-import:R0603")
      (libsource (lib "eagle-import") (part "R-US_R0603"))
    )
    (comp (ref "R19")
      (value "100.0k")
      (footprint "eagle-import:R0603")
      (libsource (lib "eagle-import") (part "R-US_R0603"))
    )
    (comp (ref "R20")
      (value "100.0k")
      (footprint "eagle-import:R0603")
      (libsource (lib "eagle-import") (part "R-US_R0603"))
    )
    (comp (ref "R21")
      (value "1.2k")
      (footprint "eagle-import:R0603")
      (libsource (lib "eagle-import") (part "R-US_R0603"))
    )
    (comp (ref "R22")
      (value "1.0M")
      (footprint "eagle-import:R0603")
      (libsource (lib "eagle-import") (part "R-US_R0603"))
    )
    (comp (ref "R23")
      (value "33.20k")
      (footprint "eagle-import:R0603")
      (libsource (lib "eagle-import") (part "R-US_R0603"))
    )
    (comp (ref "R24")
      (value "1.0M")
      (footprint "eagle-import:R0603")
      (libsource (lib "eagle-import") (part "R-US_R0603"))
    )
    (comp (ref "R26")
      (value "510")
      (footprint "eagle-import:R0603")
      (libsource (lib "eagle-import") (part "R-US_R0603"))
    )
    (comp (ref "R27")
      (value "510")
      (footprint "eagle-import:R0603")
      (libsource (lib "eagle-import") (part "R-US_R0603"))
    )
    (comp (ref "R28")
      (value "100.0k")
      (footprint "eagle-import:R0603")
      (libsource (lib "eagle-import") (part "R-US_R0603"))
    )
    (comp (ref "R29")
      (value "33.20k")
      (footprint "eagle-import:R0603")
      (libsource (lib "eagle-import") (part "R-US_R0603"))
    )
    (comp (ref "C39")
      (value "560p")
      (footprint "eagle-import:C0603")
      (libsource (lib "eagle-import") (part "C-USC0603"))
    )
    (comp (ref "C40")
      (value "560p")
      (footprint "eagle-import:C0603")
      (libsource (lib "eagle-import") (part "C-USC0603"))
    )
    (comp (ref "C44")
      (value "47p")
      (footprint "eagle-import:C0603")
      (libsource (lib "eagle-import") (part "C-USC0603"))
    )
    (comp (ref "C45")
      (value "47p")
      (footprint "eagle-import:C0603")
      (libsource (lib "eagle-import") (part "C-USC0603"))
    )
    (comp (ref "C48")
      (value "47p")
      (footprint "eagle-import:C0603")
      (libsource (lib "eagle-import") (part "C-USC0603"))
    )
    (comp (ref "J10")
      (value "PJ301_THONKICONN6")
      (footprint "eagle-import:WQP_PJ_301M6")
      (libsource (lib "eagle-import") (part "PJ301_THONKICONN6"))
    )
    (comp (ref "J11")
      (value "PJ301_THONKICONN6")
      (footprint "eagle-import:WQP_PJ_301M6")
      (libsource (lib "eagle-import") (part "PJ301_THONKICONN6"))
    )
    (comp (ref "J12")
      (value "PJ301_THONKICONN6")
      (footprint "eagle-import:WQP_PJ_301M6")
      (libsource (lib "eagle-import") (part "PJ301_THONKICONN6"))
    )
    (comp (ref "LED7")
      (value "WP7113SRSGW")
      (footprint "eagle-import:LED5MM")
      (libsource (lib "eagle-import") (part "LED5MM"))
    )
    (comp (ref "LED8")
      (value "WP937EGW")
      (footprint "eagle-import:LED3MM")
      (libsource (lib "eagle-import") (part "LED3MM"))
    )
    (comp (ref "R91")
      (value "33.20k")
      (footprint "eagle-import:R0603")
      (libsource (lib "eagle-import") (part "R-US_R0603"))
    )
    (comp (ref "R92")
      (value "100.0k")
      (footprint "eagle-import:R0603")
      (libsource (lib "eagle-import") (part "R-US_R0603"))
    )
    (comp (ref "R93")
      (value "510")
      (footprint "eagle-import:R0603")
      (libsource (lib "eagle-import") (part "R-US_R0603"))
    )
    (comp (ref "R94")
      (value "510")
      (footprint "eagle-import:R0603")
      (libsource (lib "eagle-import") (part "R-US_R0603"))
    )
    (comp (ref "R95")
      (value "100.0k")
      (footprint "eagle-import:R0603")
      (libsource (lib "eagle-import") (part "R-US_R0603"))
    )
    (comp (ref "R96")
      (value "1.0M")
      (footprint "eagle-import:R0603")
      (libsource (lib "eagle-import") (part "R-US_R0603"))
    )
    (comp (ref "R97")
      (value "10kB")
      (footprint "eagle-import:ALPS_POT_VERTICAL_PS")
      (libsource (lib "eagle-import") (part "POT_USVERTICAL_PS"))
    )
    (comp (ref "R98")
      (value "10kB")
      (footprint "eagle-import:ALPS_POT_VERTICAL")
      (libsource (lib "eagle-import") (part "POT_USVERTICAL"))
    )
    (comp (ref "R99")
      (value "4.30k")
      (footprint "eagle-import:R0603")
      (libsource (lib "eagle-import") (part "R-US_R0603"))
    )
    (comp (ref "R100")
      (value "4.30k")
      (footprint "eagle-import:R0603")
      (libsource (lib "eagle-import") (part "R-US_R0603"))
    )
    (comp (ref "R101")
      (value "100.0k")
      (footprint "eagle-import:R0603")
      (libsource (lib "eagle-import") (part "R-US_R0603"))
    )
    (comp (ref "R102")
      (value "100.0k")
      (footprint "eagle-import:R0603")
      (libsource (lib "eagle-import") (part "R-US_R0603"))
    )
    (comp (ref "R103")
      (value "33.20k")
      (footprint "eagle-import:R0603")
      (libsource (lib "eagle-import") (part "R-US_R0603"))
    )
    (comp (ref "R104")
      (value "1.0M")
      (footprint "eagle-import:R0603")
      (libsource (lib "eagle-import") (part "R-US_R0603"))
    )
    (comp (ref "R105")
      (value "100k")
      (footprint "eagle-import:R0603")
      (libsource (lib "eagle-import") (part "R-US_R0603"))
    )
    (comp (ref "R106")
      (value "100k")
      (footprint "eagle-import:R0603")
      (libsource (lib "eagle-import") (part "R-US_R0603"))
    )
    (comp (ref "R107")
      (value "66.50k")
      (footprint "eagle-import:R0603")
      (libsource (lib "eagle-import") (part "R-US_R0603"))
    )
    (comp (ref "R108")
      (value "1.2k")
      (footprint "eagle-import:R0603")
      (libsource (lib "eagle-import") (part "R-US_R0603"))
    )
    (comp (ref "R109")
      (value "100.0k")
      (footprint "eagle-import:R0603")
      (libsource (lib "eagle-import") (part "R-US_R0603"))
    )
    (comp (ref "R110")
      (value "1.0M")
      (footprint "eagle-import:R0603")
      (libsource (lib "eagle-import") (part "R-US_R0603"))
    )
    (comp (ref "R111")
      (value "100k")
      (footprint "eagle-import:R0603")
      (libsource (lib "eagle-import") (part "R-US_R0603"))
    )
    (comp (ref "R112")
      (value "100k")
      (footprint "eagle-import:R0603")
      (libsource (lib "eagle-import") (part "R-US_R0603"))
    )
    (comp (ref "R113")
      (value "1.2k")
      (footprint "eagle-import:R0603")
      (libsource (lib "eagle-import") (part "R-US_R0603"))
    )
    (comp (ref "R114")
      (value "66.50k")
      (footprint "eagle-import:R0603")
      (libsource (lib "eagle-import") (part "R-US_R0603"))
    )
    (comp (ref "R115")
      (value "1.0M")
      (footprint "eagle-import:R0603")
      (libsource (lib "eagle-import") (part "R-US_R0603"))
    )
    (comp (ref "R116")
      (value "402")
      (footprint "eagle-import:R0603")
      (libsource (lib "eagle-import") (part "R-US_R0603"))
    )
    (comp (ref "R117")
      (value "205.0k")
      (footprint "eagle-import:R0603")
      (libsource (lib "eagle-import") (part "R-US_R0603"))
    )
  )
  (nets
    (net (code "1") (name "1_TO_2") (class "Default")
      (node (ref "IC1") (pin "14") (pinfunction "OUT_14") (pintype "output"))
      (node (ref "R56") (pin "2") (pinfunction "2_2") (pintype "passive"))
      (node (ref "R8") (pin "1") (pinfunction "1_1") (pintype "passive"))
    )
    (net (code "2") (name "2_TO_3") (class "Default")
      (node (ref "IC4") (pin "14") (pinfunction "OUT_14") (pintype "output"))
      (node (ref "R41") (pin "1") (pinfunction "1_1") (pintype "passive"))
      (node (ref "R82") (pin "2") (pinfunction "2_2") (pintype "passive"))
    )
    (net (code "3") (name "3_TO_4") (class "Default")
      (node (ref "IC8") (pin "14") (pinfunction "OUT_14") (pintype "output"))
      (node (ref "R114") (pin "2") (pinfunction "2_2") (pintype "passive"))
      (node (ref "R68") (pin "1") (pinfunction "1_1") (pintype "passive"))
    )
    (net (code "4") (name "AREF_+10") (class "Default")
      (node (ref "C26") (pin "1") (pinfunction "1_1") (pintype "passive"))
      (node (ref "C28") (pin "1") (pinfunction "1_1") (pintype "passive"))
      (node (ref "C3") (pin "1") (pinfunction "1_1") (pintype "passive"))
      (node (ref "IC6") (pin "1") (pinfunction "C_1") (pintype "passive"))
      (node (ref "R1") (pin "2") (pinfunction "2_2") (pintype "passive"))
      (node (ref "R101") (pin "2") (pinfunction "2_2") (pintype "passive"))
      (node (ref "R117") (pin "2") (pinfunction "2_2") (pintype "passive"))
      (node (ref "R20") (pin "2") (pinfunction "2_2") (pintype "passive"))
      (node (ref "R3") (pin "1") (pinfunction "1_1") (pintype "passive"))
      (node (ref "R34") (pin "1") (pinfunction "1_1") (pintype "passive"))
      (node (ref "R38") (pin "2") (pinfunction "2_2") (pintype "passive"))
      (node (ref "R57") (pin "2") (pinfunction "2_2") (pintype "passive"))
      (node (ref "R59") (pin "2") (pinfunction "2_2") (pintype "passive"))
      (node (ref "R61") (pin "2") (pinfunction "2_2") (pintype "passive"))
      (node (ref "R63") (pin "1") (pinfunction "1_1") (pintype "passive"))
      (node (ref "R79") (pin "2") (pinfunction "2_2") (pintype "passive"))
      (node (ref "R95") (pin "1") (pinfunction "1_1") (pintype "passive"))
    )
    (net (code "5") (name "AREF_-10") (class "Default")
      (node (ref "C27") (pin "1") (pinfunction "1_1") (pintype "passive"))
      (node (ref "IC7") (pin "2") (pinfunction "A_2") (pintype "passive"))
      (node (ref "R109") (pin "2") (pinfunction "2_2") (pintype "passive"))
      (node (ref "R16") (pin "2") (pinfunction "2_2") (pintype "passive"))
      (node (ref "R28") (pin "2") (pinfunction "2_2") (pintype "passive"))
      (node (ref "R31") (pin "2") (pinfunction "2_2") (pintype "passive"))
      (node (ref "R49") (pin "2") (pinfunction "2_2") (pintype "passive"))
      (node (ref "R60") (pin "2") (pinfunction "2_2") (pintype "passive"))
      (node (ref "R76") (pin "2") (pinfunction "2_2") (pintype "passive"))
      (node (ref "R89") (pin "2") (pinfunction "2_2") (pintype "passive"))
      (node (ref "R92") (pin "2") (pinfunction "2_2") (pintype "passive"))
    )
    (net (code "6") (name "GND") (class "Default")
      (node (ref "C1") (pin "+") (pinfunction "+_+") (pintype "passive"))
      (node (ref "C11") (pin "2") (pinfunction "2_2") (pintype "passive"))
      (node (ref "C12") (pin "2") (pinfunction "2_2") (pintype "passive"))
      (node (ref "C13") (pin "2") (pinfunction "2_2") (pintype "passive"))
      (node (ref "C14") (pin "2") (pinfunction "2_2") (pintype "passive"))
      (node (ref "C15") (pin "2") (pinfunction "2_2") (pintype "passive"))
      (node (ref "C16") (pin "1") (pinfunction "1_1") (pintype "passive"))
      (node (ref "C17") (pin "1") (pinfunction "1_1") (pintype "passive"))
      (node (ref "C18") (pin "2") (pinfunction "2_2") (pintype "passive"))
      (node (ref "C2") (pin "-") (pinfunction "-_-") (pintype "passive"))
      (node (ref "C21") (pin "2") (pinfunction "2_2") (pintype "passive"))
      (node (ref "C22") (pin "1") (pinfunction "1_1") (pintype "passive"))
      (node (ref "C24") (pin "2") (pinfunction "2_2") (pintype "passive"))
      (node (ref "C25") (pin "2") (pinfunction "2_2") (pintype "passive"))
      (node (ref "C26") (pin "2") (pinfunction "2_2") (pintype "passive"))
      (node (ref "C27") (pin "2") (pinfunction "2_2") (pintype "passive"))
      (node (ref "C28") (pin "2") (pinfunction "2_2") (pintype "passive"))
      (node (ref "C29") (pin "1") (pinfunction "1_1") (pintype "passive"))
      (node (ref "C3") (pin "2") (pinfunction "2_2") (pintype "passive"))
      (node (ref "C30") (pin "2") (pinfunction "2_2") (pintype "passive"))
      (node (ref "C32") (pin "2") (pinfunction "2_2") (pintype "passive"))
      (node (ref "C33") (pin "1") (pinfunction "1_1") (pintype "passive"))
      (node (ref "C36") (pin "2") (pinfunction "2_2") (pintype "passive"))
      (node (ref "C37") (pin "2") (pinfunction "2_2") (pintype "passive"))
      (node (ref "C38") (pin "2") (pinfunction "2_2") (pintype "passive"))
      (node (ref "C39") (pin "2") (pinfunction "2_2") (pintype "passive"))
      (node (ref "C4") (pin "1") (pinfunction "1_1") (pintype "passive"))
      (node (ref "C40") (pin "2") (pinfunction "2_2") (pintype "passive"))
      (node (ref "C41") (pin "1") (pinfunction "1_1") (pintype "passive"))
      (node (ref "C42") (pin "1") (pinfunction "1_1") (pintype "passive"))
      (node (ref "C43") (pin "2") (pinfunction "2_2") (pintype "passive"))
      (node (ref "C46") (pin "2") (pinfunction "2_2") (pintype "passive"))
      (node (ref "C47") (pin "1") (pinfunction "1_1") (pintype "passive"))
      (node (ref "C5") (pin "2") (pinfunction "2_2") (pintype "passive"))
      (node (ref "C7") (pin "2") (pinfunction "2_2") (pintype "passive"))
      (node (ref "C8") (pin "1") (pinfunction "1_1") (pintype "passive"))
      (node (ref "D1") (pin "C") (pinfunction "C_C") (pintype "passive"))
      (node (ref "IC1") (pin "12") (pinfunction "+IN_12") (pintype "input"))
      (node (ref "IC1") (pin "3") (pinfunction "+IN_3") (pintype "input"))
      (node (ref "IC1") (pin "5") (pinfunction "+IN_5") (pintype "input"))
      (node (ref "IC10") (pin "8") (pinfunction "GND_8") (pintype "power_in"))
      (node (ref "IC11") (pin "12") (pinfunction "+IN_12") (pintype "input"))
      (node (ref "IC11") (pin "3") (pinfunction "+IN_3") (pintype "input"))
      (node (ref "IC11") (pin "5") (pinfunction "+IN_5") (pintype "input"))
      (node (ref "IC12") (pin "12") (pinfunction "+IN_12") (pintype "input"))
      (node (ref "IC12") (pin "3") (pinfunction "+IN_3") (pintype "input"))
      (node (ref "IC12") (pin "5") (pinfunction "+IN_5") (pintype "input"))
      (node (ref "IC2") (pin "12") (pinfunction "+IN_12") (pintype "input"))
      (node (ref "IC2") (pin "3") (pinfunction "+IN_3") (pintype "input"))
      (node (ref "IC2") (pin "5") (pinfunction "+IN_5") (pintype "input"))
      (node (ref "IC3") (pin "8") (pinfunction "GND_8") (pintype "power_in"))
      (node (ref "IC4") (pin "12") (pinfunction "+IN_12") (pintype "input"))
      (node (ref "IC4") (pin "3") (pinfunction "+IN_3") (pintype "input"))
      (node (ref "IC4") (pin "5") (pinfunction "+IN_5") (pintype "input"))
      (node (ref "IC5") (pin "12") (pinfunction "+IN_12") (pintype "input"))
      (node (ref "IC5") (pin "3") (pinfunction "+IN_3") (pintype "input"))
      (node (ref "IC5") (pin "5") (pinfunction "+IN_5") (pintype "input"))
      (node (ref "IC6") (pin "2") (pinfunction "A_2") (pintype "passive"))
      (node (ref "IC7") (pin "1") (pinfunction "C_1") (pintype "passive"))
      (node (ref "IC8") (pin "12") (pinfunction "+IN_12") (pintype "input"))
      (node (ref "IC8") (pin "3") (pinfunction "+IN_3") (pintype "input"))
      (node (ref "IC8") (pin "5") (pinfunction "+IN_5") (pintype "input"))
      (node (ref "IC9") (pin "12") (pinfunction "+IN_12") (pintype "input"))
      (node (ref "IC9") (pin "3") (pinfunction "+IN_3") (pintype "input"))
      (node (ref "IC9") (pin "5") (pinfunction "+IN_5") (pintype "input"))
      (node (ref "J1") (pin "P1") (pinfunction "1_P1") (pintype "passive"))
      (node (ref "J10") (pin "P1") (pinfunction "1_P1") (pintype "passive"))
      (node (ref "J11") (pin "P1") (pinfunction "1_P1") (pintype "passive"))
      (node (ref "J12") (pin "P1") (pinfunction "1_P1") (pintype "passive"))
      (node (ref "J12") (pin "P2") (pinfunction "2_P2") (pintype "passive"))
      (node (ref "J2") (pin "P1") (pinfunction "1_P1") (pintype "passive"))
      (node (ref "J3") (pin "P1") (pinfunction "1_P1") (pintype "passive"))
      (node (ref "J3") (pin "P2") (pinfunction "2_P2") (pintype "passive"))
      (node (ref "J4") (pin "P1") (pinfunction "1_P1") (pintype "passive"))
      (node (ref "J5") (pin "P1") (pinfunction "1_P1") (pintype "passive"))
      (node (ref "J6") (pin "P1") (pinfunction "1_P1") (pintype "passive"))
      (node (ref "J6") (pin "P2") (pinfunction "2_P2") (pintype "passive"))
      (node (ref "J7") (pin "P1") (pinfunction "1_P1") (pintype "passive"))
      (node (ref "J8") (pin "P1") (pinfunction "1_P1") (pintype "passive"))
      (node (ref "J9") (pin "P1") (pinfunction "1_P1") (pintype "passive"))
      (node (ref "J9") (pin "P2") (pinfunction "2_P2") (pintype "passive"))
      (node (ref "JP5") (pin "3") (pinfunction "3_3") (pintype "passive"))
      (node (ref "JP5") (pin "4") (pinfunction "4_4") (pintype "passive"))
      (node (ref "JP5") (pin "5") (pinfunction "5_5") (pintype "passive"))
      (node (ref "JP5") (pin "6") (pinfunction "6_6") (pintype "passive"))
      (node (ref "JP5") (pin "7") (pinfunction "7_7") (pintype "passive"))
      (node (ref "JP5") (pin "8") (pinfunction "8_8") (pintype "passive"))
      (node (ref "R108") (pin "2") (pinfunction "2_2") (pintype "passive"))
      (node (ref "R110") (pin "2") (pinfunction "2_2") (pintype "passive"))
      (node (ref "R113") (pin "2") (pinfunction "2_2") (pintype "passive"))
      (node (ref "R12") (pin "2") (pinfunction "2_2") (pintype "passive"))
      (node (ref "R15") (pin "2") (pinfunction "2_2") (pintype "passive"))
      (node (ref "R18") (pin "2") (pinfunction "2_2") (pintype "passive"))
      (node (ref "R21") (pin "2") (pinfunction "2_2") (pintype "passive"))
      (node (ref "R35") (pin "2") (pinfunction "2_2") (pintype "passive"))
      (node (ref "R36") (pin "P$3") (pinfunction "A_P$3") (pintype "passive"))
      (node (ref "R4") (pin "P$3") (pinfunction "A_P$3") (pintype "passive"))
      (node (ref "R48") (pin "2") (pinfunction "2_2") (pintype "passive"))
      (node (ref "R52") (pin "2") (pinfunction "2_2") (pintype "passive"))
      (node (ref "R53") (pin "2") (pinfunction "2_2") (pintype "passive"))
      (node (ref "R64") (pin "P$3") (pinfunction "A_P$3") (pintype "passive"))
      (node (ref "R72") (pin "2") (pinfunction "2_2") (pintype "passive"))
      (node (ref "R75") (pin "2") (pinfunction "2_2") (pintype "passive"))
      (node (ref "R77") (pin "2") (pinfunction "2_2") (pintype "passive"))
      (node (ref "R80") (pin "2") (pinfunction "2_2") (pintype "passive"))
      (node (ref "R96") (pin "2") (pinfunction "2_2") (pintype "passive"))
      (node (ref "R97") (pin "P$3") (pinfunction "A_P$3") (pintype "passive"))
    )
    (net (code "7") (name "Net-(C12-Pad1)") (class "Default")
      (node (ref "C12") (pin "1") (pinfunction "1_1") (pintype "passive"))
      (node (ref "R26") (pin "1") (pinfunction "1_1") (pintype "passive"))
    )
    (net (code "8") (name "Net-(C13-Pad1)") (class "Default")
      (node (ref "C13") (pin "1") (pinfunction "1_1") (pintype "passive"))
      (node (ref "R27") (pin "1") (pinfunction "1_1") (pintype "passive"))
    )
    (net (code "9") (name "Net-(C14-Pad1)") (class "Default")
      (node (ref "C14") (pin "1") (pinfunction "1_1") (pintype "passive"))
      (node (ref "R33") (pin "1") (pinfunction "1_1") (pintype "passive"))
    )
    (net (code "10") (name "Net-(C15-Pad1)") (class "Default")
      (node (ref "C15") (pin "1") (pinfunction "1_1") (pintype "passive"))
      (node (ref "R32") (pin "1") (pinfunction "1_1") (pintype "passive"))
    )
    (net (code "11") (name "Net-(C37-Pad1)") (class "Default")
      (node (ref "C37") (pin "1") (pinfunction "1_1") (pintype "passive"))
      (node (ref "R87") (pin "1") (pinfunction "1_1") (pintype "passive"))
    )
    (net (code "12") (name "Net-(C38-Pad1)") (class "Default")
      (node (ref "C38") (pin "1") (pinfunction "1_1") (pintype "passive"))
      (node (ref "R88") (pin "1") (pinfunction "1_1") (pintype "passive"))
    )
    (net (code "13") (name "Net-(C39-Pad1)") (class "Default")
      (node (ref "C39") (pin "1") (pinfunction "1_1") (pintype "passive"))
      (node (ref "R94") (pin "1") (pinfunction "1_1") (pintype "passive"))
    )
    (net (code "14") (name "Net-(C40-Pad1)") (class "Default")
      (node (ref "C40") (pin "1") (pinfunction "1_1") (pintype "passive"))
      (node (ref "R93") (pin "1") (pinfunction "1_1") (pintype "passive"))
    )
    (net (code "15") (name "Net-(D2-PadA)") (class "Default")
      (node (ref "D2") (pin "A") (pinfunction "A_A") (pintype "passive"))
      (node (ref "JP5") (pin "1") (pinfunction "1_1") (pintype "passive"))
      (node (ref "JP5") (pin "2") (pinfunction "2_2") (pintype "passive"))
    )
    (net (code "16") (name "Net-(D2-PadC)") (class "Default")
      (node (ref "D2") (pin "C") (pinfunction "C_C") (pintype "passive"))
      (node (ref "L1") (pin "2") (pinfunction "2_2") (pintype "passive"))
    )
    (net (code "17") (name "Net-(IC1A--IN)") (class "Default")
      (node (ref "IC1") (pin "2") (pinfunction "-IN_2") (pintype "input"))
      (node (ref "IC3") (pin "13") (pinfunction "OUT_13") (pintype "output"))
      (node (ref "R7") (pin "2") (pinfunction "2_2") (pintype "passive"))
    )
    (net (code "18") (name "Net-(IC1A-OUT)") (class "Default")
      (node (ref "IC1") (pin "1") (pinfunction "OUT_1") (pintype "output"))
      (node (ref "R13") (pin "2") (pinfunction "2_2") (pintype "passive"))
      (node (ref "R7") (pin "1") (pinfunction "1_1") (pintype "passive"))
    )
    (net (code "19") (name "Net-(IC1B--IN)") (class "Default")
      (node (ref "C9") (pin "1") (pinfunction "1_1") (pintype "passive"))
      (node (ref "IC1") (pin "6") (pinfunction "-IN_6") (pintype "input"))
      (node (ref "R13") (pin "1") (pinfunction "1_1") (pintype "passive"))
      (node (ref "R14") (pin "2") (pinfunction "2_2") (pintype "passive"))
      (node (ref "R23") (pin "1") (pinfunction "1_1") (pintype "passive"))
    )
    (net (code "20") (name "Net-(IC1B-OUT)") (class "Default")
      (node (ref "C9") (pin "2") (pinfunction "2_2") (pintype "passive"))
      (node (ref "IC1") (pin "7") (pinfunction "OUT_7") (pintype "output"))
      (node (ref "R14") (pin "1") (pinfunction "1_1") (pintype "passive"))
      (node (ref "R17") (pin "2") (pinfunction "2_2") (pintype "passive"))
      (node (ref "R24") (pin "2") (pinfunction "2_2") (pintype "passive"))
    )
    (net (code "21") (name "Net-(IC1C-+IN)") (class "Default")
      (node (ref "IC1") (pin "10") (pinfunction "+IN_10") (pintype "input"))
      (node (ref "R18") (pin "1") (pinfunction "1_1") (pintype "passive"))
      (node (ref "R24") (pin "1") (pinfunction "1_1") (pintype "passive"))
    )
    (net (code "22") (name "Net-(IC1C--IN)") (class "Default")
      (node (ref "IC1") (pin "9") (pinfunction "-IN_9") (pintype "input"))
      (node (ref "LED1") (pin "A") (pinfunction "A_A") (pintype "passive"))
      (node (ref "R15") (pin "1") (pinfunction "1_1") (pintype "passive"))
    )
    (net (code "23") (name "Net-(IC1C-OUT)") (class "Default")
      (node (ref "IC1") (pin "8") (pinfunction "OUT_8") (pintype "output"))
      (node (ref "LED1") (pin "K") (pinfunction "C_K") (pintype "passive"))
    )
    (net (code "24") (name "Net-(IC1D--IN)") (class "Default")
      (node (ref "IC1") (pin "13") (pinfunction "-IN_13") (pintype "input"))
      (node (ref "R10") (pin "1") (pinfunction "1_1") (pintype "passive"))
      (node (ref "R8") (pin "2") (pinfunction "2_2") (pintype "passive"))
    )
    (net (code "25") (name "Net-(IC2A--IN)") (class "Default")
      (node (ref "C6") (pin "2") (pinfunction "2_2") (pintype "passive"))
      (node (ref "IC2") (pin "2") (pinfunction "-IN_2") (pintype "input"))
      (node (ref "R1") (pin "1") (pinfunction "1_1") (pintype "passive"))
      (node (ref "R2") (pin "1") (pinfunction "1_1") (pintype "passive"))
      (node (ref "R4") (pin "P$1") (pinfunction "E_P$1") (pintype "passive"))
      (node (ref "R5") (pin "P$3") (pinfunction "A_P$3") (pintype "passive"))
      (node (ref "R6") (pin "2") (pinfunction "2_2") (pintype "passive"))
    )
    (net (code "26") (name "Net-(IC2A-OUT)") (class "Default")
      (node (ref "C6") (pin "1") (pinfunction "1_1") (pintype "passive"))
      (node (ref "IC2") (pin "1") (pinfunction "OUT_1") (pintype "output"))
      (node (ref "R22") (pin "2") (pinfunction "2_2") (pintype "passive"))
      (node (ref "R23") (pin "2") (pinfunction "2_2") (pintype "passive"))
      (node (ref "R29") (pin "2") (pinfunction "2_2") (pintype "passive"))
      (node (ref "R6") (pin "1") (pinfunction "1_1") (pintype "passive"))
    )
    (net (code "27") (name "Net-(IC2B--IN)") (class "Default")
      (node (ref "C10") (pin "1") (pinfunction "1_1") (pintype "passive"))
      (node (ref "IC2") (pin "6") (pinfunction "-IN_6") (pintype "input"))
      (node (ref "IC3") (pin "4") (pinfunction "OUT_4") (pintype "output"))
      (node (ref "R19") (pin "1") (pinfunction "1_1") (pintype "passive"))
      (node (ref "R20") (pin "1") (pinfunction "1_1") (pintype "passive"))
    )
    (net (code "28") (name "Net-(IC2B-OUT)") (class "Default")
      (node (ref "C10") (pin "2") (pinfunction "2_2") (pintype "passive"))
      (node (ref "IC2") (pin "7") (pinfunction "OUT_7") (pintype "output"))
      (node (ref "IC3") (pin "14") (pinfunction "CTRL_14") (pintype "input"))
      (node (ref "IC3") (pin "3") (pinfunction "CTRL_3") (pintype "input"))
    )
    (net (code "29") (name "Net-(IC2C-+IN)") (class "Default")
      (node (ref "IC2") (pin "10") (pinfunction "+IN_10") (pintype "input"))
      (node (ref "R12") (pin "1") (pinfunction "1_1") (pintype "passive"))
      (node (ref "R22") (pin "1") (pinfunction "1_1") (pintype "passive"))
    )
    (net (code "30") (name "Net-(IC2C--IN)") (class "Default")
      (node (ref "IC2") (pin "9") (pinfunction "-IN_9") (pintype "input"))
      (node (ref "LED2") (pin "A") (pinfunction "A_A") (pintype "passive"))
      (node (ref "R21") (pin "1") (pinfunction "1_1") (pintype "passive"))
    )
    (net (code "31") (name "Net-(IC2C-OUT)") (class "Default")
      (node (ref "IC2") (pin "8") (pinfunction "OUT_8") (pintype "output"))
      (node (ref "LED2") (pin "K") (pinfunction "C_K") (pintype "passive"))
    )
    (net (code "32") (name "Net-(IC2D--IN)") (class "Default")
      (node (ref "IC2") (pin "13") (pinfunction "-IN_13") (pintype "input"))
      (node (ref "R5") (pin "P$1") (pinfunction "E_P$1") (pintype "passive"))
      (node (ref "R9") (pin "2") (pinfunction "2_2") (pintype "passive"))
    )
    (net (code "33") (name "Net-(IC2D-OUT)") (class "Default")
      (node (ref "IC2") (pin "14") (pinfunction "OUT_14") (pintype "output"))
      (node (ref "R2") (pin "2") (pinfunction "2_2") (pintype "passive"))
      (node (ref "R9") (pin "1") (pinfunction "1_1") (pintype "passive"))
    )
    (net (code "34") (name "Net-(IC3A-IN)") (class "Default")
      (node (ref "IC3") (pin "2") (pinfunction "IN_2") (pintype "input"))
      (node (ref "R27") (pin "2") (pinfunction "2_2") (pintype "passive"))
      (node (ref "R28") (pin "1") (pinfunction "1_1") (pintype "passive"))
    )
    (net (code "35") (name "Net-(IC3B-CTRL)") (class "Default")
      (node (ref "C19") (pin "2") (pinfunction "2_2") (pintype "passive"))
      (node (ref "IC3") (pin "11") (pinfunction "CTRL_11") (pintype "input"))
      (node (ref "IC3") (pin "6") (pinfunction "CTRL_6") (pintype "input"))
      (node (ref "IC5") (pin "1") (pinfunction "OUT_1") (pintype "output"))
    )
    (net (code "36") (name "Net-(IC3B-IN)") (class "Default")
      (node (ref "IC3") (pin "7") (pinfunction "IN_7") (pintype "input"))
      (node (ref "R31") (pin "1") (pinfunction "1_1") (pintype "passive"))
      (node (ref "R33") (pin "2") (pinfunction "2_2") (pintype "passive"))
    )
    (net (code "37") (name "Net-(IC3B-OUT)") (class "Default")
      (node (ref "C19") (pin "1") (pinfunction "1_1") (pintype "passive"))
      (node (ref "IC3") (pin "5") (pinfunction "OUT_5") (pintype "output"))
      (node (ref "IC5") (pin "2") (pinfunction "-IN_2") (pintype "input"))
      (node (ref "R38") (pin "1") (pinfunction "1_1") (pintype "passive"))
      (node (ref "R39") (pin "1") (pinfunction "1_1") (pintype "passive"))
    )
    (net (code "38") (name "Net-(IC3C-IN)") (class "Default")
      (node (ref "IC3") (pin "10") (pinfunction "IN_10") (pintype "input"))
      (node (ref "R30") (pin "1") (pinfunction "1_1") (pintype "passive"))
      (node (ref "R32") (pin "2") (pinfunction "2_2") (pintype "passive"))
    )
    (net (code "39") (name "Net-(IC3C-OUT)") (class "Default")
      (node (ref "IC3") (pin "12") (pinfunction "OUT_12") (pintype "output"))
      (node (ref "IC4") (pin "2") (pinfunction "-IN_2") (pintype "input"))
      (node (ref "R40") (pin "2") (pinfunction "2_2") (pintype "passive"))
    )
    (net (code "40") (name "Net-(IC3D-IN)") (class "Default")
      (node (ref "IC3") (pin "15") (pinfunction "IN_15") (pintype "input"))
      (node (ref "R26") (pin "2") (pinfunction "2_2") (pintype "passive"))
      (node (ref "R29") (pin "1") (pinfunction "1_1") (pintype "passive"))
    )
    (net (code "41") (name "Net-(IC3E-MODE)") (class "Default")
      (node (ref "IC3") (pin "1") (pinfunction "MODE_1") (pintype "input"))
      (node (ref "R25") (pin "2") (pinfunction "2_2") (pintype "passive"))
    )
    (net (code "42") (name "Net-(IC4A-OUT)") (class "Default")
      (node (ref "IC4") (pin "1") (pinfunction "OUT_1") (pintype "output"))
      (node (ref "R40") (pin "1") (pinfunction "1_1") (pintype "passive"))
      (node (ref "R46") (pin "2") (pinfunction "2_2") (pintype "passive"))
    )
    (net (code "43") (name "Net-(IC4B--IN)") (class "Default")
      (node (ref "C20") (pin "1") (pinfunction "1_1") (pintype "passive"))
      (node (ref "IC4") (pin "6") (pinfunction "-IN_6") (pintype "input"))
      (node (ref "R46") (pin "1") (pinfunction "1_1") (pintype "passive"))
      (node (ref "R47") (pin "2") (pinfunction "2_2") (pintype "passive"))
      (node (ref "R54") (pin "1") (pinfunction "1_1") (pintype "passive"))
      (node (ref "R56") (pin "1") (pinfunction "1_1") (pintype "passive"))
    )
    (net (code "44") (name "Net-(IC4B-OUT)") (class "Default")
      (node (ref "C20") (pin "2") (pinfunction "2_2") (pintype "passive"))
      (node (ref "IC4") (pin "7") (pinfunction "OUT_7") (pintype "output"))
      (node (ref "R47") (pin "1") (pinfunction "1_1") (pintype "passive"))
      (node (ref "R55") (pin "2") (pinfunction "2_2") (pintype "passive"))
      (node (ref "R58") (pin "2") (pinfunction "2_2") (pintype "passive"))
    )
    (net (code "45") (name "Net-(IC4C-+IN)") (class "Default")
      (node (ref "IC4") (pin "10") (pinfunction "+IN_10") (pintype "input"))
      (node (ref "R52") (pin "1") (pinfunction "1_1") (pintype "passive"))
      (node (ref "R58") (pin "1") (pinfunction "1_1") (pintype "passive"))
    )
    (net (code "46") (name "Net-(IC4C--IN)") (class "Default")
      (node (ref "IC4") (pin "9") (pinfunction "-IN_9") (pintype "input"))
      (node (ref "LED3") (pin "A") (pinfunction "A_A") (pintype "passive"))
      (node (ref "R48") (pin "1") (pinfunction "1_1") (pintype "passive"))
    )
    (net (code "47") (name "Net-(IC4C-OUT)") (class "Default")
      (node (ref "IC4") (pin "8") (pinfunction "OUT_8") (pintype "output"))
      (node (ref "LED3") (pin "K") (pinfunction "C_K") (pintype "passive"))
    )
    (net (code "48") (name "Net-(IC4D--IN)") (class "Default")
      (node (ref "IC4") (pin "13") (pinfunction "-IN_13") (pintype "input"))
      (node (ref "R41") (pin "2") (pinfunction "2_2") (pintype "passive"))
      (node (ref "R44") (pin "1") (pinfunction "1_1") (pintype "passive"))
    )
    (net (code "49") (name "Net-(IC5B--IN)") (class "Default")
      (node (ref "C23") (pin "2") (pinfunction "2_2") (pintype "passive"))
      (node (ref "IC5") (pin "6") (pinfunction "-IN_6") (pintype "input"))
      (node (ref "R36") (pin "P$1") (pinfunction "E_P$1") (pintype "passive"))
      (node (ref "R37") (pin "P$3") (pinfunction "A_P$3") (pintype "passive"))
      (node (ref "R50") (pin "1") (pinfunction "1_1") (pintype "passive"))
      (node (ref "R51") (pin "2") (pinfunction "2_2") (pintype "passive"))
      (node (ref "R57") (pin "1") (pinfunction "1_1") (pintype "passive"))
    )
    (net (code "50") (name "Net-(IC5B-OUT)") (class "Default")
      (node (ref "C23") (pin "1") (pinfunction "1_1") (pintype "passive"))
      (node (ref "IC5") (pin "7") (pinfunction "OUT_7") (pintype "output"))
      (node (ref "R30") (pin "2") (pinfunction "2_2") (pintype "passive"))
      (node (ref "R42") (pin "2") (pinfunction "2_2") (pintype "passive"))
      (node (ref "R51") (pin "1") (pinfunction "1_1") (pintype "passive"))
      (node (ref "R54") (pin "2") (pinfunction "2_2") (pintype "passive"))
    )
    (net (code "51") (name "Net-(IC5C-+IN)") (class "Default")
      (node (ref "IC5") (pin "10") (pinfunction "+IN_10") (pintype "input"))
      (node (ref "R35") (pin "1") (pinfunction "1_1") (pintype "passive"))
      (node (ref "R42") (pin "1") (pinfunction "1_1") (pintype "passive"))
    )
    (net (code "52") (name "Net-(IC5C--IN)") (class "Default")
      (node (ref "IC5") (pin "9") (pinfunction "-IN_9") (pintype "input"))
      (node (ref "LED4") (pin "A") (pinfunction "A_A") (pintype "passive"))
      (node (ref "R53") (pin "1") (pinfunction "1_1") (pintype "passive"))
    )
    (net (code "53") (name "Net-(IC5C-OUT)") (class "Default")
      (node (ref "IC5") (pin "8") (pinfunction "OUT_8") (pintype "output"))
      (node (ref "LED4") (pin "K") (pinfunction "C_K") (pintype "passive"))
    )
    (net (code "54") (name "Net-(IC5D--IN)") (class "Default")
      (node (ref "IC5") (pin "13") (pinfunction "-IN_13") (pintype "input"))
      (node (ref "R37") (pin "P$1") (pinfunction "E_P$1") (pintype "passive"))
      (node (ref "R43") (pin "2") (pinfunction "2_2") (pintype "passive"))
    )
    (net (code "55") (name "Net-(IC5D-OUT)") (class "Default")
      (node (ref "IC5") (pin "14") (pinfunction "OUT_14") (pintype "output"))
      (node (ref "R43") (pin "1") (pinfunction "1_1") (pintype "passive"))
      (node (ref "R50") (pin "2") (pinfunction "2_2") (pintype "passive"))
    )
    (net (code "56") (name "Net-(IC8A-OUT)") (class "Default")
      (node (ref "IC8") (pin "1") (pinfunction "OUT_1") (pintype "output"))
      (node (ref "R67") (pin "1") (pinfunction "1_1") (pintype "passive"))
      (node (ref "R73") (pin "2") (pinfunction "2_2") (pintype "passive"))
    )
    (net (code "57") (name "Net-(IC8B--IN)") (class "Default")
      (node (ref "C34") (pin "1") (pinfunction "1_1") (pintype "passive"))
      (node (ref "IC8") (pin "6") (pinfunction "-IN_6") (pintype "input"))
      (node (ref "R73") (pin "1") (pinfunction "1_1") (pintype "passive"))
      (node (ref "R74") (pin "2") (pinfunction "2_2") (pintype "passive"))
      (node (ref "R82") (pin "1") (pinfunction "1_1") (pintype "passive"))
      (node (ref "R83") (pin "1") (pinfunction "1_1") (pintype "passive"))
    )
    (net (code "58") (name "Net-(IC8B-OUT)") (class "Default")
      (node (ref "C34") (pin "2") (pinfunction "2_2") (pintype "passive"))
      (node (ref "IC8") (pin "7") (pinfunction "OUT_7") (pintype "output"))
      (node (ref "R74") (pin "1") (pinfunction "1_1") (pintype "passive"))
      (node (ref "R84") (pin "2") (pinfunction "2_2") (pintype "passive"))
      (node (ref "R85") (pin "2") (pinfunction "2_2") (pintype "passive"))
    )
    (net (code "59") (name "Net-(IC8C-+IN)") (class "Default")
      (node (ref "IC8") (pin "10") (pinfunction "+IN_10") (pintype "input"))
      (node (ref "R77") (pin "1") (pinfunction "1_1") (pintype "passive"))
      (node (ref "R85") (pin "1") (pinfunction "1_1") (pintype "passive"))
    )
    (net (code "60") (name "Net-(IC8C--IN)") (class "Default")
      (node (ref "IC8") (pin "9") (pinfunction "-IN_9") (pintype "input"))
      (node (ref "LED5") (pin "A") (pinfunction "A_A") (pintype "passive"))
      (node (ref "R75") (pin "1") (pinfunction "1_1") (pintype "passive"))
    )
    (net (code "61") (name "Net-(IC8C-OUT)") (class "Default")
      (node (ref "IC8") (pin "8") (pinfunction "OUT_8") (pintype "output"))
      (node (ref "LED5") (pin "K") (pinfunction "C_K") (pintype "passive"))
    )
    (net (code "62") (name "Net-(IC8D--IN)") (class "Default")
      (node (ref "IC8") (pin "13") (pinfunction "-IN_13") (pintype "input"))
      (node (ref "R68") (pin "2") (pinfunction "2_2") (pintype "passive"))
      (node (ref "R70") (pin "1") (pinfunction "1_1") (pintype "passive"))
    )
    (net (code "63") (name "Net-(IC9A--IN)") (class "Default")
      (node (ref "C31") (pin "2") (pinfunction "2_2") (pintype "passive"))
      (node (ref "IC9") (pin "2") (pinfunction "-IN_2") (pintype "input"))
      (node (ref "R61") (pin "1") (pinfunction "1_1") (pintype "passive"))
      (node (ref "R62") (pin "1") (pinfunction "1_1") (pintype "passive"))
      (node (ref "R64") (pin "P$1") (pinfunction "E_P$1") (pintype "passive"))
      (node (ref "R65") (pin "P$3") (pinfunction "A_P$3") (pintype "passive"))
      (node (ref "R66") (pin "2") (pinfunction "2_2") (pintype "passive"))
    )
    (net (code "64") (name "Net-(IC9A-OUT)") (class "Default")
      (node (ref "C31") (pin "1") (pinfunction "1_1") (pintype "passive"))
      (node (ref "IC9") (pin "1") (pinfunction "OUT_1") (pintype "output"))
      (node (ref "R66") (pin "1") (pinfunction "1_1") (pintype "passive"))
      (node (ref "R81") (pin "2") (pinfunction "2_2") (pintype "passive"))
      (node (ref "R83") (pin "2") (pinfunction "2_2") (pintype "passive"))
      (node (ref "R90") (pin "2") (pinfunction "2_2") (pintype "passive"))
    )
    (net (code "65") (name "Net-(IC9C-+IN)") (class "Default")
      (node (ref "IC9") (pin "10") (pinfunction "+IN_10") (pintype "input"))
      (node (ref "R72") (pin "1") (pinfunction "1_1") (pintype "passive"))
      (node (ref "R81") (pin "1") (pinfunction "1_1") (pintype "passive"))
    )
    (net (code "66") (name "Net-(IC9C--IN)") (class "Default")
      (node (ref "IC9") (pin "9") (pinfunction "-IN_9") (pintype "input"))
      (node (ref "LED6") (pin "A") (pinfunction "A_A") (pintype "passive"))
      (node (ref "R80") (pin "1") (pinfunction "1_1") (pintype "passive"))
    )
    (net (code "67") (name "Net-(IC9C-OUT)") (class "Default")
      (node (ref "IC9") (pin "8") (pinfunction "OUT_8") (pintype "output"))
      (node (ref "LED6") (pin "K") (pinfunction "C_K") (pintype "passive"))
    )
    (net (code "68") (name "Net-(IC9D--IN)") (class "Default")
      (node (ref "IC9") (pin "13") (pinfunction "-IN_13") (pintype "input"))
      (node (ref "R65") (pin "P$1") (pinfunction "E_P$1") (pintype "passive"))
      (node (ref "R69") (pin "2") (pinfunction "2_2") (pintype "passive"))
    )
    (net (code "69") (name "Net-(IC9D-OUT)") (class "Default")
      (node (ref "IC9") (pin "14") (pinfunction "OUT_14") (pintype "output"))
      (node (ref "R62") (pin "2") (pinfunction "2_2") (pintype "passive"))
      (node (ref "R69") (pin "1") (pinfunction "1_1") (pintype "passive"))
    )
    (net (code "70") (name "Net-(IC10A-CTRL)") (class "Default")
      (node (ref "C35") (pin "2") (pinfunction "2_2") (pintype "passive"))
      (node (ref "IC10") (pin "14") (pinfunction "CTRL_14") (pintype "input"))
      (node (ref "IC10") (pin "3") (pinfunction "CTRL_3") (pintype "input"))
      (node (ref "IC9") (pin "7") (pinfunction "OUT_7") (pintype "output"))
    )
    (net (code "71") (name "Net-(IC10A-IN)") (class "Default")
      (node (ref "IC10") (pin "2") (pinfunction "IN_2") (pintype "input"))
      (node (ref "R88") (pin "2") (pinfunction "2_2") (pintype "passive"))
      (node (ref "R89") (pin "1") (pinfunction "1_1") (pintype "passive"))
    )
    (net (code "72") (name "Net-(IC10A-OUT)") (class "Default")
      (node (ref "C35") (pin "1") (pinfunction "1_1") (pintype "passive"))
      (node (ref "IC10") (pin "4") (pinfunction "OUT_4") (pintype "output"))
      (node (ref "IC9") (pin "6") (pinfunction "-IN_6") (pintype "input"))
      (node (ref "R78") (pin "1") (pinfunction "1_1") (pintype "passive"))
      (node (ref "R79") (pin "1") (pinfunction "1_1") (pintype "passive"))
    )
    (net (code "73") (name "Net-(IC10B-CTRL)") (class "Default")
      (node (ref "C44") (pin "2") (pinfunction "2_2") (pintype "passive"))
      (node (ref "IC10") (pin "11") (pinfunction "CTRL_11") (pintype "input"))
      (node (ref "IC10") (pin "6") (pinfunction "CTRL_6") (pintype "input"))
      (node (ref "IC12") (pin "1") (pinfunction "OUT_1") (pintype "output"))
    )
    (net (code "74") (name "Net-(IC10B-IN)") (class "Default")
      (node (ref "IC10") (pin "7") (pinfunction "IN_7") (pintype "input"))
      (node (ref "R92") (pin "1") (pinfunction "1_1") (pintype "passive"))
      (node (ref "R94") (pin "2") (pinfunction "2_2") (pintype "passive"))
    )
    (net (code "75") (name "Net-(IC10B-OUT)") (class "Default")
      (node (ref "C44") (pin "1") (pinfunction "1_1") (pintype "passive"))
      (node (ref "IC10") (pin "5") (pinfunction "OUT_5") (pintype "output"))
      (node (ref "IC12") (pin "2") (pinfunction "-IN_2") (pintype "input"))
      (node (ref "R101") (pin "1") (pinfunction "1_1") (pintype "passive"))
      (node (ref "R102") (pin "1") (pinfunction "1_1") (pintype "passive"))
    )
    (net (code "76") (name "Net-(IC10C-IN)") (class "Default")
      (node (ref "IC10") (pin "10") (pinfunction "IN_10") (pintype "input"))
      (node (ref "R91") (pin "1") (pinfunction "1_1") (pintype "passive"))
      (node (ref "R93") (pin "2") (pinfunction "2_2") (pintype "passive"))
    )
    (net (code "77") (name "Net-(IC10C-OUT)") (class "Default")
      (node (ref "IC10") (pin "12") (pinfunction "OUT_12") (pintype "output"))
      (node (ref "IC11") (pin "2") (pinfunction "-IN_2") (pintype "input"))
      (node (ref "R100") (pin "2") (pinfunction "2_2") (pintype "passive"))
    )
    (net (code "78") (name "Net-(IC10D-IN)") (class "Default")
      (node (ref "IC10") (pin "15") (pinfunction "IN_15") (pintype "input"))
      (node (ref "R87") (pin "2") (pinfunction "2_2") (pintype "passive"))
      (node (ref "R90") (pin "1") (pinfunction "1_1") (pintype "passive"))
    )
    (net (code "79") (name "Net-(IC10D-OUT)") (class "Default")
      (node (ref "IC10") (pin "13") (pinfunction "OUT_13") (pintype "output"))
      (node (ref "IC8") (pin "2") (pinfunction "-IN_2") (pintype "input"))
      (node (ref "R67") (pin "2") (pinfunction "2_2") (pintype "passive"))
    )
    (net (code "80") (name "Net-(IC10E-MODE)") (class "Default")
      (node (ref "IC10") (pin "1") (pinfunction "MODE_1") (pintype "input"))
      (node (ref "R86") (pin "2") (pinfunction "2_2") (pintype "passive"))
    )
    (net (code "81") (name "Net-(IC11A-OUT)") (class "Default")
      (node (ref "IC11") (pin "1") (pinfunction "OUT_1") (pintype "output"))
      (node (ref "R100") (pin "1") (pinfunction "1_1") (pintype "passive"))
      (node (ref "R99") (pin "2") (pinfunction "2_2") (pintype "passive"))
    )
    (net (code "82") (name "Net-(IC11B--IN)") (class "Default")
      (node (ref "C45") (pin "1") (pinfunction "1_1") (pintype "passive"))
      (node (ref "IC11") (pin "6") (pinfunction "-IN_6") (pintype "input"))
      (node (ref "R103") (pin "1") (pinfunction "1_1") (pintype "passive"))
      (node (ref "R107") (pin "2") (pinfunction "2_2") (pintype "passive"))
      (node (ref "R114") (pin "1") (pinfunction "1_1") (pintype "passive"))
      (node (ref "R99") (pin "1") (pinfunction "1_1") (pintype "passive"))
    )
    (net (code "83") (name "Net-(IC11B-OUT)") (class "Default")
      (node (ref "C45") (pin "2") (pinfunction "2_2") (pintype "passive"))
      (node (ref "IC11") (pin "7") (pinfunction "OUT_7") (pintype "output"))
      (node (ref "R107") (pin "1") (pinfunction "1_1") (pintype "passive"))
      (node (ref "R115") (pin "2") (pinfunction "2_2") (pintype "passive"))
      (node (ref "R116") (pin "2") (pinfunction "2_2") (pintype "passive"))
    )
    (net (code "84") (name "Net-(IC11C-+IN)") (class "Default")
      (node (ref "IC11") (pin "10") (pinfunction "+IN_10") (pintype "input"))
      (node (ref "R110") (pin "1") (pinfunction "1_1") (pintype "passive"))
      (node (ref "R115") (pin "1") (pinfunction "1_1") (pintype "passive"))
    )
    (net (code "85") (name "Net-(IC11C--IN)") (class "Default")
      (node (ref "IC11") (pin "9") (pinfunction "-IN_9") (pintype "input"))
      (node (ref "LED7") (pin "A") (pinfunction "A_A") (pintype "passive"))
      (node (ref "R108") (pin "1") (pinfunction "1_1") (pintype "passive"))
    )
    (net (code "86") (name "Net-(IC11C-OUT)") (class "Default")
      (node (ref "IC11") (pin "8") (pinfunction "OUT_8") (pintype "output"))
      (node (ref "LED7") (pin "K") (pinfunction "C_K") (pintype "passive"))
    )
    (net (code "87") (name "Net-(IC11D--IN)") (class "Default")
      (node (ref "IC11") (pin "13") (pinfunction "-IN_13") (pintype "input"))
      (node (ref "IC11") (pin "14") (pinfunction "OUT_14") (pintype "output"))
    )
    (net (code "88") (name "Net-(IC12B--IN)") (class "Default")
      (node (ref "C48") (pin "2") (pinfunction "2_2") (pintype "passive"))
      (node (ref "IC12") (pin "6") (pinfunction "-IN_6") (pintype "input"))
      (node (ref "R111") (pin "1") (pinfunction "1_1") (pintype "passive"))
      (node (ref "R112") (pin "2") (pinfunction "2_2") (pintype "passive"))
      (node (ref "R117") (pin "1") (pinfunction "1_1") (pintype "passive"))
      (node (ref "R97") (pin "P$1") (pinfunction "E_P$1") (pintype "passive"))
      (node (ref "R98") (pin "P$3") (pinfunction "A_P$3") (pintype "passive"))
    )
    (net (code "89") (name "Net-(IC12B-OUT)") (class "Default")
      (node (ref "C48") (pin "1") (pinfunction "1_1") (pintype "passive"))
      (node (ref "IC12") (pin "7") (pinfunction "OUT_7") (pintype "output"))
      (node (ref "R103") (pin "2") (pinfunction "2_2") (pintype "passive"))
      (node (ref "R104") (pin "2") (pinfunction "2_2") (pintype "passive"))
      (node (ref "R112") (pin "1") (pinfunction "1_1") (pintype "passive"))
      (node (ref "R91") (pin "2") (pinfunction "2_2") (pintype "passive"))
    )
    (net (code "90") (name "Net-(IC12C-+IN)") (class "Default")
      (node (ref "IC12") (pin "10") (pinfunction "+IN_10") (pintype "input"))
      (node (ref "R104") (pin "1") (pinfunction "1_1") (pintype "passive"))
      (node (ref "R96") (pin "1") (pinfunction "1_1") (pintype "passive"))
    )
    (net (code "91") (name "Net-(IC12C--IN)") (class "Default")
      (node (ref "IC12") (pin "9") (pinfunction "-IN_9") (pintype "input"))
      (node (ref "LED8") (pin "A") (pinfunction "A_A") (pintype "passive"))
      (node (ref "R113") (pin "1") (pinfunction "1_1") (pintype "passive"))
    )
    (net (code "92") (name "Net-(IC12C-OUT)") (class "Default")
      (node (ref "IC12") (pin "8") (pinfunction "OUT_8") (pintype "output"))
      (node (ref "LED8") (pin "K") (pinfunction "C_K") (pintype "passive"))
    )
    (net (code "93") (name "Net-(IC12D--IN)") (class "Default")
      (node (ref "IC12") (pin "13") (pinfunction "-IN_13") (pintype "input"))
      (node (ref "R105") (pin "2") (pinfunction "2_2") (pintype "passive"))
      (node (ref "R98") (pin "P$1") (pinfunction "E_P$1") (pintype "passive"))
    )
    (net (code "94") (name "Net-(IC12D-OUT)") (class "Default")
      (node (ref "IC12") (pin "14") (pinfunction "OUT_14") (pintype "output"))
      (node (ref "R105") (pin "1") (pinfunction "1_1") (pintype "passive"))
      (node (ref "R111") (pin "2") (pinfunction "2_2") (pintype "passive"))
    )
    (net (code "95") (name "Net-(J1-2)") (class "Default")
      (node (ref "J1") (pin "P2") (pinfunction "2_P2") (pintype "passive"))
      (node (ref "R3") (pin "2") (pinfunction "2_2") (pintype "passive"))
    )
    (net (code "96") (name "Net-(J1-3)") (class "Default")
      (node (ref "J1") (pin "P3") (pinfunction "3_P3") (pintype "passive"))
      (node (ref "R19") (pin "2") (pinfunction "2_2") (pintype "passive"))
    )
    (net (code "97") (name "Net-(J2-2)") (class "Default")
      (node (ref "J2") (pin "P2") (pinfunction "2_P2") (pintype "passive"))
      (node (ref "R10") (pin "2") (pinfunction "2_2") (pintype "passive"))
    )
    (net (code "98") (name "Net-(J2-3)") (class "Default")
      (node (ref "J2") (pin "P3") (pinfunction "3_P3") (pintype "passive"))
      (node (ref "R17") (pin "1") (pinfunction "1_1") (pintype "passive"))
    )
    (net (code "99") (name "Net-(J3-3)") (class "Default")
      (node (ref "J3") (pin "P3") (pinfunction "3_P3") (pintype "passive"))
      (node (ref "R11") (pin "2") (pinfunction "2_2") (pintype "passive"))
    )
    (net (code "100") (name "Net-(J4-2)") (class "Default")
      (node (ref "J4") (pin "P2") (pinfunction "2_P2") (pintype "passive"))
      (node (ref "R34") (pin "2") (pinfunction "2_2") (pintype "passive"))
    )
    (net (code "101") (name "Net-(J4-3)") (class "Default")
      (node (ref "J4") (pin "P3") (pinfunction "3_P3") (pintype "passive"))
      (node (ref "R39") (pin "2") (pinfunction "2_2") (pintype "passive"))
    )
    (net (code "102") (name "Net-(J5-2)") (class "Default")
      (node (ref "J5") (pin "P2") (pinfunction "2_P2") (pintype "passive"))
      (node (ref "R44") (pin "2") (pinfunction "2_2") (pintype "passive"))
    )
    (net (code "103") (name "Net-(J5-3)") (class "Default")
      (node (ref "J5") (pin "P3") (pinfunction "3_P3") (pintype "passive"))
      (node (ref "R55") (pin "1") (pinfunction "1_1") (pintype "passive"))
    )
    (net (code "104") (name "Net-(J6-3)") (class "Default")
      (node (ref "J6") (pin "P3") (pinfunction "3_P3") (pintype "passive"))
      (node (ref "R45") (pin "2") (pinfunction "2_2") (pintype "passive"))
    )
    (net (code "105") (name "Net-(J7-2)") (class "Default")
      (node (ref "J7") (pin "P2") (pinfunction "2_P2") (pintype "passive"))
      (node (ref "R63") (pin "2") (pinfunction "2_2") (pintype "passive"))
    )
    (net (code "106") (name "Net-(J7-3)") (class "Default")
      (node (ref "J7") (pin "P3") (pinfunction "3_P3") (pintype "passive"))
      (node (ref "R78") (pin "2") (pinfunction "2_2") (pintype "passive"))
    )
    (net (code "107") (name "Net-(J8-2)") (class "Default")
      (node (ref "J8") (pin "P2") (pinfunction "2_P2") (pintype "passive"))
      (node (ref "R70") (pin "2") (pinfunction "2_2") (pintype "passive"))
    )
    (net (code "108") (name "Net-(J8-3)") (class "Default")
      (node (ref "J8") (pin "P3") (pinfunction "3_P3") (pintype "passive"))
      (node (ref "R84") (pin "1") (pinfunction "1_1") (pintype "passive"))
    )
    (net (code "109") (name "Net-(J9-3)") (class "Default")
      (node (ref "J9") (pin "P3") (pinfunction "3_P3") (pintype "passive"))
      (node (ref "R71") (pin "2") (pinfunction "2_2") (pintype "passive"))
    )
    (net (code "110") (name "Net-(J10-2)") (class "Default")
      (node (ref "J10") (pin "P2") (pinfunction "2_P2") (pintype "passive"))
      (node (ref "R95") (pin "2") (pinfunction "2_2") (pintype "passive"))
    )
    (net (code "111") (name "Net-(J10-3)") (class "Default")
      (node (ref "J10") (pin "P3") (pinfunction "3_P3") (pintype "passive"))
      (node (ref "R102") (pin "2") (pinfunction "2_2") (pintype "passive"))
    )
    (net (code "112") (name "Net-(J11-3)") (class "Default")
      (node (ref "J11") (pin "P3") (pinfunction "3_P3") (pintype "passive"))
      (node (ref "R116") (pin "1") (pinfunction "1_1") (pintype "passive"))
    )
    (net (code "113") (name "Net-(J12-3)") (class "Default")
      (node (ref "J12") (pin "P3") (pinfunction "3_P3") (pintype "passive"))
      (node (ref "R106") (pin "2") (pinfunction "2_2") (pintype "passive"))
    )
    (net (code "114") (name "Net-(JP5-Pad10)") (class "Default")
      (node (ref "JP5") (pin "10") (pinfunction "10_10") (pintype "passive"))
      (node (ref "JP5") (pin "9") (pinfunction "9_9") (pintype "passive"))
      (node (ref "P1") (pin "2") (pinfunction "2_2") (pintype "bidirectional"))
    )
    (net (code "115") (name "Net-(L2-Pad2)") (class "Default")
      (node (ref "L2") (pin "2") (pinfunction "2_2") (pintype "passive"))
      (node (ref "P1") (pin "1") (pinfunction "1_1") (pintype "bidirectional"))
    )
    (net (code "116") (name "Net-(R4-S)") (class "Default")
      (node (ref "R16") (pin "1") (pinfunction "1_1") (pintype "passive"))
      (node (ref "R4") (pin "P$2") (pinfunction "S_P$2") (pintype "passive"))
    )
    (net (code "117") (name "Net-(R5-S)") (class "Default")
      (node (ref "R11") (pin "1") (pinfunction "1_1") (pintype "passive"))
      (node (ref "R5") (pin "P$2") (pinfunction "S_P$2") (pintype "passive"))
    )
    (net (code "118") (name "Net-(R36-S)") (class "Default")
      (node (ref "R36") (pin "P$2") (pinfunction "S_P$2") (pintype "passive"))
      (node (ref "R49") (pin "1") (pinfunction "1_1") (pintype "passive"))
    )
    (net (code "119") (name "Net-(R37-S)") (class "Default")
      (node (ref "R37") (pin "P$2") (pinfunction "S_P$2") (pintype "passive"))
      (node (ref "R45") (pin "1") (pinfunction "1_1") (pintype "passive"))
    )
    (net (code "120") (name "Net-(R64-S)") (class "Default")
      (node (ref "R64") (pin "P$2") (pinfunction "S_P$2") (pintype "passive"))
      (node (ref "R76") (pin "1") (pinfunction "1_1") (pintype "passive"))
    )
    (net (code "121") (name "Net-(R65-S)") (class "Default")
      (node (ref "R65") (pin "P$2") (pinfunction "S_P$2") (pintype "passive"))
      (node (ref "R71") (pin "1") (pinfunction "1_1") (pintype "passive"))
    )
    (net (code "122") (name "Net-(R97-S)") (class "Default")
      (node (ref "R109") (pin "1") (pinfunction "1_1") (pintype "passive"))
      (node (ref "R97") (pin "P$2") (pinfunction "S_P$2") (pintype "passive"))
    )
    (net (code "123") (name "Net-(R98-S)") (class "Default")
      (node (ref "R106") (pin "1") (pinfunction "1_1") (pintype "passive"))
      (node (ref "R98") (pin "P$2") (pinfunction "S_P$2") (pintype "passive"))
    )
    (net (code "124") (name "VCC") (class "Default")
      (node (ref "C11") (pin "1") (pinfunction "1_1") (pintype "passive"))
      (node (ref "C18") (pin "1") (pinfunction "1_1") (pintype "passive"))
      (node (ref "C2") (pin "+") (pinfunction "+_+") (pintype "passive"))
      (node (ref "C21") (pin "1") (pinfunction "1_1") (pintype "passive"))
      (node (ref "C24") (pin "1") (pinfunction "1_1") (pintype "passive"))
      (node (ref "C30") (pin "1") (pinfunction "1_1") (pintype "passive"))
      (node (ref "C32") (pin "1") (pinfunction "1_1") (pintype "passive"))
      (node (ref "C36") (pin "1") (pinfunction "1_1") (pintype "passive"))
      (node (ref "C43") (pin "1") (pinfunction "1_1") (pintype "passive"))
      (node (ref "C46") (pin "1") (pinfunction "1_1") (pintype "passive"))
      (node (ref "C5") (pin "1") (pinfunction "1_1") (pintype "passive"))
      (node (ref "C7") (pin "1") (pinfunction "1_1") (pintype "passive"))
      (node (ref "IC1") (pin "4") (pinfunction "V+_4") (pintype "power_in"))
      (node (ref "IC10") (pin "16") (pinfunction "V+_16") (pintype "power_in"))
      (node (ref "IC11") (pin "4") (pinfunction "V+_4") (pintype "power_in"))
      (node (ref "IC12") (pin "4") (pinfunction "V+_4") (pintype "power_in"))
      (node (ref "IC2") (pin "4") (pinfunction "V+_4") (pintype "power_in"))
      (node (ref "IC3") (pin "16") (pinfunction "V+_16") (pintype "power_in"))
      (node (ref "IC4") (pin "4") (pinfunction "V+_4") (pintype "power_in"))
      (node (ref "IC5") (pin "4") (pinfunction "V+_4") (pintype "power_in"))
      (node (ref "IC8") (pin "4") (pinfunction "V+_4") (pintype "power_in"))
      (node (ref "IC9") (pin "4") (pinfunction "V+_4") (pintype "power_in"))
      (node (ref "L1") (pin "1") (pinfunction "1_1") (pintype "passive"))
      (node (ref "R25") (pin "1") (pinfunction "1_1") (pintype "passive"))
      (node (ref "R59") (pin "1") (pinfunction "1_1") (pintype "passive"))
      (node (ref "R86") (pin "1") (pinfunction "1_1") (pintype "passive"))
    )
    (net (code "125") (name "VEE") (class "Default")
      (node (ref "C1") (pin "-") (pinfunction "-_-") (pintype "passive"))
      (node (ref "C16") (pin "2") (pinfunction "2_2") (pintype "passive"))
      (node (ref "C17") (pin "2") (pinfunction "2_2") (pintype "passive"))
      (node (ref "C22") (pin "2") (pinfunction "2_2") (pintype "passive"))
      (node (ref "C25") (pin "1") (pinfunction "1_1") (pintype "passive"))
      (node (ref "C29") (pin "2") (pinfunction "2_2") (pintype "passive"))
      (node (ref "C33") (pin "2") (pinfunction "2_2") (pintype "passive"))
      (node (ref "C4") (pin "2") (pinfunction "2_2") (pintype "passive"))
      (node (ref "C41") (pin "2") (pinfunction "2_2") (pintype "passive"))
      (node (ref "C42") (pin "2") (pinfunction "2_2") (pintype "passive"))
      (node (ref "C47") (pin "2") (pinfunction "2_2") (pintype "passive"))
      (node (ref "C8") (pin "2") (pinfunction "2_2") (pintype "passive"))
      (node (ref "D1") (pin "A") (pinfunction "A_A") (pintype "passive"))
      (node (ref "IC1") (pin "11") (pinfunction "V-_11") (pintype "power_in"))
      (node (ref "IC10") (pin "9") (pinfunction "V-_9") (pintype "power_in"))
      (node (ref "IC11") (pin "11") (pinfunction "V-_11") (pintype "power_in"))
      (node (ref "IC12") (pin "11") (pinfunction "V-_11") (pintype "power_in"))
      (node (ref "IC2") (pin "11") (pinfunction "V-_11") (pintype "power_in"))
      (node (ref "IC3") (pin "9") (pinfunction "V-_9") (pintype "power_in"))
      (node (ref "IC4") (pin "11") (pinfunction "V-_11") (pintype "power_in"))
      (node (ref "IC5") (pin "11") (pinfunction "V-_11") (pintype "power_in"))
      (node (ref "IC8") (pin "11") (pinfunction "V-_11") (pintype "power_in"))
      (node (ref "IC9") (pin "11") (pinfunction "V-_11") (pintype "power_in"))
      (node (ref "L2") (pin "1") (pinfunction "1_1") (pintype "passive"))
      (node (ref "R60") (pin "1") (pinfunction "1_1") (pintype "passive"))
    )
    (net (code "126") (name "unconnected-(J11-2-PadP2)") (class "Default")
      (node (ref "J11") (pin "P2") (pinfunction "2_P2") (pintype "passive"))
    )
  )
)
